# IPBUS_mezzanine.net
KiCad netlist of a schematic drawn in Altium Designer
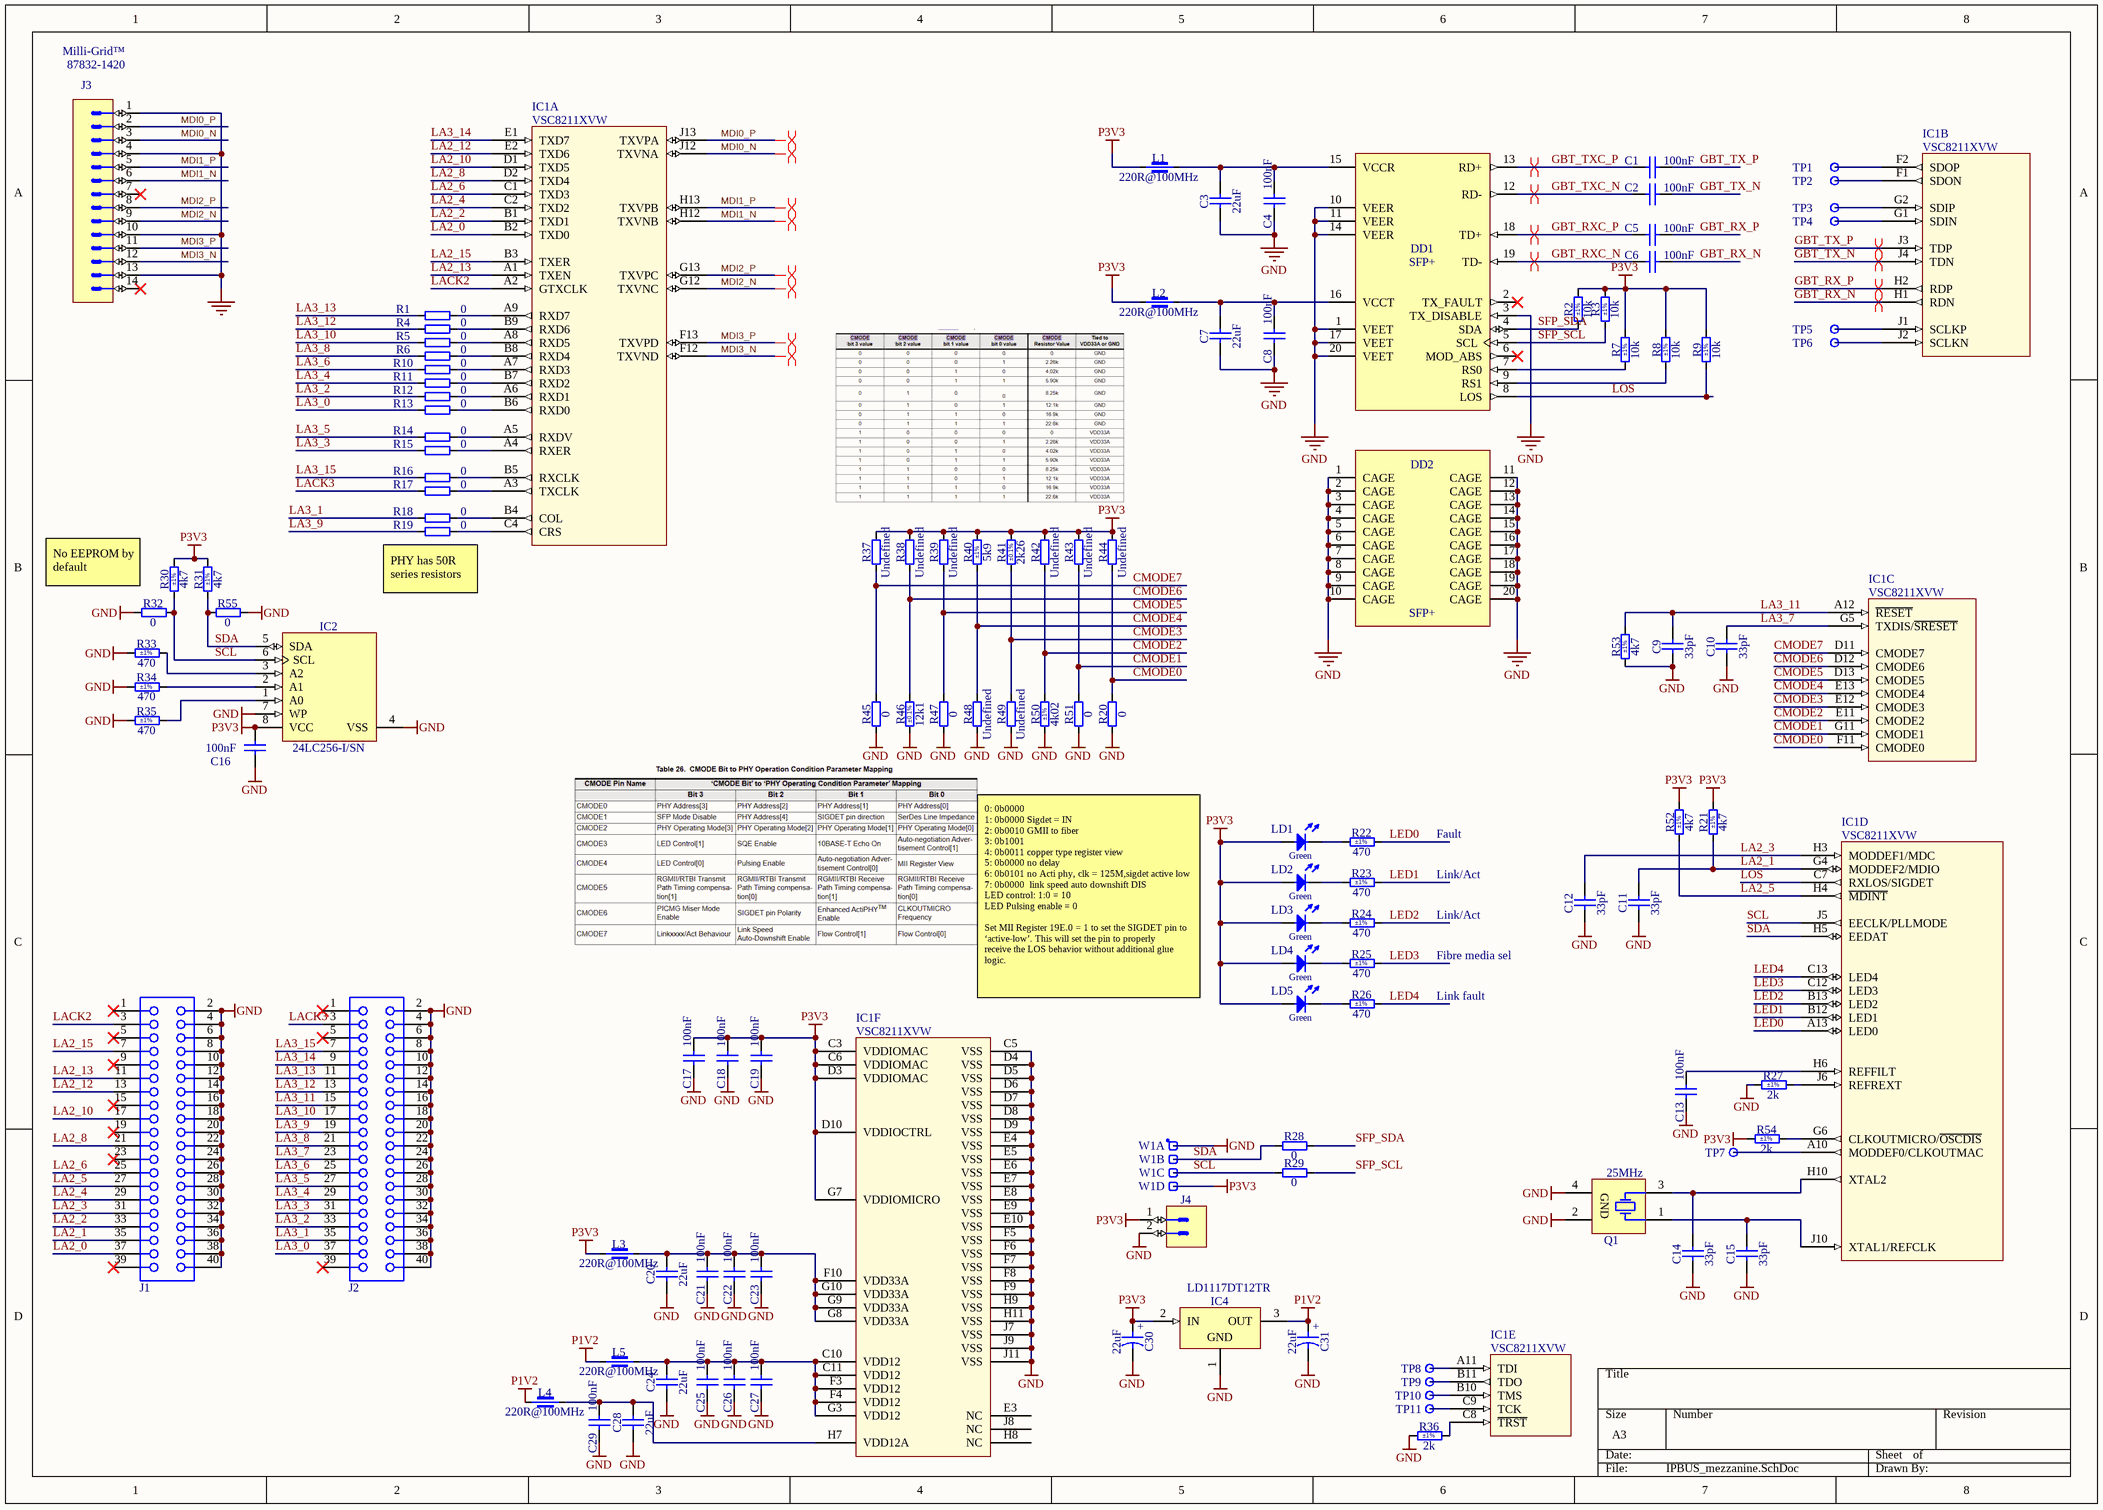
[diagram p0: IPBUS_mezzanine.SchDoc]

(export (version "E")
  (design (tool "Eeschema 10.0.6"))
  (components
    (comp (ref "C1")
      (value "100nF")
      (footprint "CAPC1005X55N")
      (description "Non-polarised capacitor")
      (fields
        (field (name "PART NUMBER") "CC0402_100NF_16V_10%_X5R")
        (field (name "VOLTAGE") "16V")
        (field (name "AUTHOR") "CERN DEM JLC")
      )
      (libsource (lib "Capacitors") (part "Capacitor - non polarized"))
    )
    (comp (ref "C2")
      (value "100nF")
      (footprint "CAPC1005X55N")
      (description "Non-polarised capacitor")
      (fields
        (field (name "PART NUMBER") "CC0402_100NF_16V_10%_X5R")
        (field (name "VOLTAGE") "16V")
        (field (name "AUTHOR") "CERN DEM JLC")
      )
      (libsource (lib "Capacitors") (part "Capacitor - non polarized"))
    )
    (comp (ref "C3")
      (value "22uF")
      (footprint "CAPC3216X180N")
      (description "Non-polarised capacitor")
      (fields
        (field (name "PART NUMBER") "CC1206_22UF_25V_20%_X5R")
        (field (name "VOLTAGE") "25V")
        (field (name "AUTHOR") "CERN DEM WB")
      )
      (libsource (lib "Capacitors") (part "Capacitor - non polarized"))
    )
    (comp (ref "C4")
      (value "100nF")
      (footprint "CAPC1005X55N")
      (description "Non-polarised capacitor")
      (fields
        (field (name "PART NUMBER") "CC0402_100NF_16V_10%_X5R")
        (field (name "VOLTAGE") "16V")
        (field (name "AUTHOR") "CERN DEM JLC")
      )
      (libsource (lib "Capacitors") (part "Capacitor - non polarized"))
    )
    (comp (ref "C5")
      (value "100nF")
      (footprint "CAPC1005X55N")
      (description "Non-polarised capacitor")
      (fields
        (field (name "PART NUMBER") "CC0402_100NF_16V_10%_X5R")
        (field (name "VOLTAGE") "16V")
        (field (name "AUTHOR") "CERN DEM JLC")
      )
      (libsource (lib "Capacitors") (part "Capacitor - non polarized"))
    )
    (comp (ref "C6")
      (value "100nF")
      (footprint "CAPC1005X55N")
      (description "Non-polarised capacitor")
      (fields
        (field (name "PART NUMBER") "CC0402_100NF_16V_10%_X5R")
        (field (name "VOLTAGE") "16V")
        (field (name "AUTHOR") "CERN DEM JLC")
      )
      (libsource (lib "Capacitors") (part "Capacitor - non polarized"))
    )
    (comp (ref "C7")
      (value "22uF")
      (footprint "CAPC3216X180N")
      (description "Non-polarised capacitor")
      (fields
        (field (name "PART NUMBER") "CC1206_22UF_25V_20%_X5R")
        (field (name "VOLTAGE") "25V")
        (field (name "AUTHOR") "CERN DEM WB")
      )
      (libsource (lib "Capacitors") (part "Capacitor - non polarized"))
    )
    (comp (ref "C8")
      (value "100nF")
      (footprint "CAPC1005X55N")
      (description "Non-polarised capacitor")
      (fields
        (field (name "PART NUMBER") "CC0402_100NF_16V_10%_X5R")
        (field (name "VOLTAGE") "16V")
        (field (name "AUTHOR") "CERN DEM JLC")
      )
      (libsource (lib "Capacitors") (part "Capacitor - non polarized"))
    )
    (comp (ref "C9")
      (value "33pF")
      (footprint "CAPC1005X55N")
      (description "Non-polarised capacitor")
      (fields
        (field (name "PART NUMBER") "CC0402_33PF_50V_5%_C0G")
        (field (name "VOLTAGE") "50V")
        (field (name "AUTHOR") "CERN DEM JLC")
      )
      (libsource (lib "Capacitors") (part "Capacitor - non polarized"))
    )
    (comp (ref "C10")
      (value "33pF")
      (footprint "CAPC1005X55N")
      (description "Non-polarised capacitor")
      (fields
        (field (name "PART NUMBER") "CC0402_33PF_50V_5%_C0G")
        (field (name "VOLTAGE") "50V")
        (field (name "AUTHOR") "CERN DEM JLC")
      )
      (libsource (lib "Capacitors") (part "Capacitor - non polarized"))
    )
    (comp (ref "C11")
      (value "33pF")
      (footprint "CAPC1005X55N")
      (description "Non-polarised capacitor")
      (fields
        (field (name "PART NUMBER") "CC0402_33PF_50V_5%_C0G")
        (field (name "VOLTAGE") "50V")
        (field (name "AUTHOR") "CERN DEM JLC")
      )
      (libsource (lib "Capacitors") (part "Capacitor - non polarized"))
    )
    (comp (ref "C12")
      (value "33pF")
      (footprint "CAPC1005X55N")
      (description "Non-polarised capacitor")
      (fields
        (field (name "PART NUMBER") "CC0402_33PF_50V_5%_C0G")
        (field (name "VOLTAGE") "50V")
        (field (name "AUTHOR") "CERN DEM JLC")
      )
      (libsource (lib "Capacitors") (part "Capacitor - non polarized"))
    )
    (comp (ref "C13")
      (value "100nF")
      (footprint "CAPC1005X55N")
      (description "Non-polarised capacitor")
      (fields
        (field (name "PART NUMBER") "CC0402_100NF_16V_10%_X5R")
        (field (name "VOLTAGE") "16V")
        (field (name "AUTHOR") "CERN DEM JLC")
      )
      (libsource (lib "Capacitors") (part "Capacitor - non polarized"))
    )
    (comp (ref "C14")
      (value "33pF")
      (footprint "CAPC1005X55N")
      (description "Non-polarised capacitor")
      (fields
        (field (name "PART NUMBER") "CC0402_33PF_50V_5%_C0G")
        (field (name "VOLTAGE") "50V")
        (field (name "AUTHOR") "CERN DEM JLC")
      )
      (libsource (lib "Capacitors") (part "Capacitor - non polarized"))
    )
    (comp (ref "C15")
      (value "33pF")
      (footprint "CAPC1005X55N")
      (description "Non-polarised capacitor")
      (fields
        (field (name "PART NUMBER") "CC0402_33PF_50V_5%_C0G")
        (field (name "VOLTAGE") "50V")
        (field (name "AUTHOR") "CERN DEM JLC")
      )
      (libsource (lib "Capacitors") (part "Capacitor - non polarized"))
    )
    (comp (ref "C16")
      (value "100nF")
      (footprint "CAPC1005X55N")
      (description "Non-polarised capacitor")
      (fields
        (field (name "PART NUMBER") "CC0402_100NF_16V_10%_X5R")
        (field (name "VOLTAGE") "16V")
        (field (name "AUTHOR") "CERN DEM JLC")
      )
      (libsource (lib "Capacitors") (part "Capacitor - non polarized"))
    )
    (comp (ref "C17")
      (value "100nF")
      (footprint "CAPC1005X55N")
      (description "Non-polarised capacitor")
      (fields
        (field (name "PART NUMBER") "CC0402_100NF_16V_10%_X5R")
        (field (name "VOLTAGE") "16V")
        (field (name "AUTHOR") "CERN DEM JLC")
      )
      (libsource (lib "Capacitors") (part "Capacitor - non polarized"))
    )
    (comp (ref "C18")
      (value "100nF")
      (footprint "CAPC1005X55N")
      (description "Non-polarised capacitor")
      (fields
        (field (name "PART NUMBER") "CC0402_100NF_16V_10%_X5R")
        (field (name "VOLTAGE") "16V")
        (field (name "AUTHOR") "CERN DEM JLC")
      )
      (libsource (lib "Capacitors") (part "Capacitor - non polarized"))
    )
    (comp (ref "C19")
      (value "100nF")
      (footprint "CAPC1005X55N")
      (description "Non-polarised capacitor")
      (fields
        (field (name "PART NUMBER") "CC0402_100NF_16V_10%_X5R")
        (field (name "VOLTAGE") "16V")
        (field (name "AUTHOR") "CERN DEM JLC")
      )
      (libsource (lib "Capacitors") (part "Capacitor - non polarized"))
    )
    (comp (ref "C20")
      (value "22uF")
      (footprint "CAPC3216X180N")
      (description "Non-polarised capacitor")
      (fields
        (field (name "PART NUMBER") "CC1206_22UF_25V_20%_X5R")
        (field (name "VOLTAGE") "25V")
        (field (name "AUTHOR") "CERN DEM WB")
      )
      (libsource (lib "Capacitors") (part "Capacitor - non polarized"))
    )
    (comp (ref "C21")
      (value "100nF")
      (footprint "CAPC1005X55N")
      (description "Non-polarised capacitor")
      (fields
        (field (name "PART NUMBER") "CC0402_100NF_16V_10%_X5R")
        (field (name "VOLTAGE") "16V")
        (field (name "AUTHOR") "CERN DEM JLC")
      )
      (libsource (lib "Capacitors") (part "Capacitor - non polarized"))
    )
    (comp (ref "C22")
      (value "100nF")
      (footprint "CAPC1005X55N")
      (description "Non-polarised capacitor")
      (fields
        (field (name "PART NUMBER") "CC0402_100NF_16V_10%_X5R")
        (field (name "VOLTAGE") "16V")
        (field (name "AUTHOR") "CERN DEM JLC")
      )
      (libsource (lib "Capacitors") (part "Capacitor - non polarized"))
    )
    (comp (ref "C23")
      (value "100nF")
      (footprint "CAPC1005X55N")
      (description "Non-polarised capacitor")
      (fields
        (field (name "PART NUMBER") "CC0402_100NF_16V_10%_X5R")
        (field (name "VOLTAGE") "16V")
        (field (name "AUTHOR") "CERN DEM JLC")
      )
      (libsource (lib "Capacitors") (part "Capacitor - non polarized"))
    )
    (comp (ref "C24")
      (value "22uF")
      (footprint "CAPC3216X180N")
      (description "Non-polarised capacitor")
      (fields
        (field (name "PART NUMBER") "CC1206_22UF_25V_20%_X5R")
        (field (name "VOLTAGE") "25V")
        (field (name "AUTHOR") "CERN DEM WB")
      )
      (libsource (lib "Capacitors") (part "Capacitor - non polarized"))
    )
    (comp (ref "C25")
      (value "100nF")
      (footprint "CAPC1005X55N")
      (description "Non-polarised capacitor")
      (fields
        (field (name "PART NUMBER") "CC0402_100NF_16V_10%_X5R")
        (field (name "VOLTAGE") "16V")
        (field (name "AUTHOR") "CERN DEM JLC")
      )
      (libsource (lib "Capacitors") (part "Capacitor - non polarized"))
    )
    (comp (ref "C26")
      (value "100nF")
      (footprint "CAPC1005X55N")
      (description "Non-polarised capacitor")
      (fields
        (field (name "PART NUMBER") "CC0402_100NF_16V_10%_X5R")
        (field (name "VOLTAGE") "16V")
        (field (name "AUTHOR") "CERN DEM JLC")
      )
      (libsource (lib "Capacitors") (part "Capacitor - non polarized"))
    )
    (comp (ref "C27")
      (value "100nF")
      (footprint "CAPC1005X55N")
      (description "Non-polarised capacitor")
      (fields
        (field (name "PART NUMBER") "CC0402_100NF_16V_10%_X5R")
        (field (name "VOLTAGE") "16V")
        (field (name "AUTHOR") "CERN DEM JLC")
      )
      (libsource (lib "Capacitors") (part "Capacitor - non polarized"))
    )
    (comp (ref "C28")
      (value "22uF")
      (footprint "CAPC3216X180N")
      (description "Non-polarised capacitor")
      (fields
        (field (name "PART NUMBER") "CC1206_22UF_25V_20%_X5R")
        (field (name "VOLTAGE") "25V")
        (field (name "AUTHOR") "CERN DEM WB")
      )
      (libsource (lib "Capacitors") (part "Capacitor - non polarized"))
    )
    (comp (ref "C29")
      (value "100nF")
      (footprint "CAPC1005X55N")
      (description "Non-polarised capacitor")
      (fields
        (field (name "PART NUMBER") "CC0402_100NF_16V_10%_X5R")
        (field (name "VOLTAGE") "16V")
        (field (name "AUTHOR") "CERN DEM JLC")
      )
      (libsource (lib "Capacitors") (part "Capacitor - non polarized"))
    )
    (comp (ref "C30")
      (value "22uF")
      (footprint "CAPMP3528X210N")
      (description "Polarised capacitor")
      (fields
        (field (name "PART NUMBER") "CTE3528-21_22UF_10V_10%_LESR0700")
        (field (name "VOLTAGE") "10V")
        (field (name "AUTHOR") "CERN DEM JLC")
      )
      (libsource (lib "Capacitors") (part "Capacitor - polarized"))
    )
    (comp (ref "C31")
      (value "22uF")
      (footprint "CAPMP3528X210N")
      (description "Polarised capacitor")
      (fields
        (field (name "PART NUMBER") "CTE3528-21_22UF_10V_10%_LESR0700")
        (field (name "VOLTAGE") "10V")
        (field (name "AUTHOR") "CERN DEM JLC")
      )
      (libsource (lib "Capacitors") (part "Capacitor - polarized"))
    )
    (comp (ref "DD1")
      (value "SFP+")
      (footprint "AMPHENOL_UE76A203000")
      (description "20 Position SFP+ Connector (Small Form-factor Pluggable)")
      (fields
        (field (name "PART NUMBER") "AMPHENOL_UE76A203000")
        (field (name "MANUFACTURER") "AMPHENOL")
        (field (name "AUTHOR") "CERN DEM BC")
      )
      (libsource (lib "Connectors") (part "SFP+x1"))
    )
    (comp (ref "DD2")
      (value "SFP+")
      (footprint "AMPHENOL_U77A16131001")
      (description "SFP+ 1x1 Cage (20Pins)")
      (fields
        (field (name "PART NUMBER") "AMPHENOL_U77A16131001")
        (field (name "MANUFACTURER") "AMPHENOL")
        (field (name "AUTHOR") "CERN DEM BC")
      )
      (libsource (lib "Connectors") (part "SFP+ 1x1 Cage (20Pins)"))
    )
    (comp (ref "IC1")
      (value "VSC8211XVW")
      (footprint "BGA117C100P13X9_1400X1000X170")
      (fields (field (name "MANUFACTURER") "VITESSE SEMICONDUCTOR") (field (name "AUTHOR") "CERN DEM JLC"))
      (libsource (lib "ICs And Semiconductors") (part "VSC8211XVW"))
    )
    (comp (ref "IC2")
      (value "24LC256-I/SN")
      (footprint "SOIC127P600X175-8N")
      (description "2.5V-5.5V, 256K (32k x 8-bit) I2C Serial EEPROM")
      (fields (field (name "MANUFACTURER") "MICROCHIP TECHNOLOGY") (field (name "AUTHOR") "CERN DEM JLC"))
      (libsource (lib "ICs And Semiconductors") (part "24LC256-I/SN"))
    )
    (comp (ref "IC4")
      (value "LD1117DT12TR")
      (footprint "TO228P972X240-3N-R540X510")
      (description "3-Terminal Regulator 1=GND 2=IN 3=OUT")
      (fields (field (name "MANUFACTURER") "ST MICROELECTRONICS") (field (name "AUTHOR") "CERN DEM JLC"))
      (libsource (lib "ICs And Semiconductors") (part "REG3 1GND-2IN-3OUT"))
    )
    (comp (ref "J1")
      (value "61304021821")
      (footprint "61304021821")
      (description "WR-PHD Socket Header, THT, Vertical, pitch 2.54mm, 2 Row, 40P")
      (fields (field (name "MANUFACTURER") "Wurth Elektronik"))
      (libsource (lib "Altium_WR-PHD (rev24a)") (part "61304021821"))
    )
    (comp (ref "J2")
      (value "61304021821")
      (footprint "61304021821")
      (description "WR-PHD Socket Header, THT, Vertical, pitch 2.54mm, 2 Row, 40P")
      (fields (field (name "MANUFACTURER") "Wurth Elektronik"))
      (libsource (lib "Altium_WR-PHD (rev24a)") (part "61304021821"))
    )
    (comp (ref "J3")
      (value "Milli-Grid™")
      (footprint "MOLEX_87832-1420")
      (description "Connector 14 Male")
      (fields
        (field (name "MANUFACTURER PART NUMBER") "87832-1420")
        (field (name "MANUFACTURER") "MOLEX")
        (field (name "PART NUMBER") "MOLEX_87832-1420")
        (field (name "AUTHOR") "CERN DEM JLC")
      )
      (libsource (lib "Connectors") (part "Connector 14 Male"))
    )
    (comp (ref "J4")
      (value "KK®")
      (footprint "MOLEX_22-05-7028")
      (description "Connector 2 Male")
      (fields
        (field (name "PART NUMBER") "MOLEX_22-05-7028")
        (field (name "MANUFACTURER") "MOLEX")
        (field (name "AUTHOR") "CERN DEM JLC")
      )
      (libsource (lib "Connectors") (part "Connector 2 Male"))
    )
    (comp (ref "L1")
      (value "220R@100MHz")
      (footprint "INDC1608X95N")
      (fields
        (field (name "PART NUMBER") "IND0603_MURATA_BLM18SG221TN1")
        (field (name "POWER") "2.5A")
        (field (name "TOLERANCE") "±25%")
        (field (name "AUTHOR") "CERN DEM MR")
      )
      (libsource (lib "Inductors & Transformers") (part "Ferrite Bead"))
    )
    (comp (ref "L2")
      (value "220R@100MHz")
      (footprint "INDC1608X95N")
      (fields
        (field (name "PART NUMBER") "IND0603_MURATA_BLM18SG221TN1")
        (field (name "POWER") "2.5A")
        (field (name "TOLERANCE") "±25%")
        (field (name "AUTHOR") "CERN DEM MR")
      )
      (libsource (lib "Inductors & Transformers") (part "Ferrite Bead"))
    )
    (comp (ref "L3")
      (value "220R@100MHz")
      (footprint "INDC1608X95N")
      (fields
        (field (name "PART NUMBER") "IND0603_MURATA_BLM18SG221TN1")
        (field (name "POWER") "2.5A")
        (field (name "TOLERANCE") "±25%")
        (field (name "AUTHOR") "CERN DEM MR")
      )
      (libsource (lib "Inductors & Transformers") (part "Ferrite Bead"))
    )
    (comp (ref "L4")
      (value "220R@100MHz")
      (footprint "INDC1608X95N")
      (fields
        (field (name "PART NUMBER") "IND0603_MURATA_BLM18SG221TN1")
        (field (name "POWER") "2.5A")
        (field (name "TOLERANCE") "±25%")
        (field (name "AUTHOR") "CERN DEM MR")
      )
      (libsource (lib "Inductors & Transformers") (part "Ferrite Bead"))
    )
    (comp (ref "L5")
      (value "220R@100MHz")
      (footprint "INDC1608X95N")
      (fields
        (field (name "PART NUMBER") "IND0603_MURATA_BLM18SG221TN1")
        (field (name "POWER") "2.5A")
        (field (name "TOLERANCE") "±25%")
        (field (name "AUTHOR") "CERN DEM MR")
      )
      (libsource (lib "Inductors & Transformers") (part "Ferrite Bead"))
    )
    (comp (ref "LD1")
      (value "Green")
      (footprint "LED_AVAGO_HSME-C120")
      (description "LED Green 1C 2A")
      (fields
        (field (name "PART NUMBER") "LED_AVAGO_HSME-C120")
        (field (name "MANUFACTURER") "AVAGO TECHNOLOGIES")
        (field (name "AUTHOR") "CERN DEM JMW")
      )
      (libsource (lib "ICs And Semiconductors") (part "LED Green 1C 2A"))
    )
    (comp (ref "LD2")
      (value "Green")
      (footprint "LED_AVAGO_HSME-C120")
      (description "LED Green 1C 2A")
      (fields
        (field (name "PART NUMBER") "LED_AVAGO_HSME-C120")
        (field (name "MANUFACTURER") "AVAGO TECHNOLOGIES")
        (field (name "AUTHOR") "CERN DEM JMW")
      )
      (libsource (lib "ICs And Semiconductors") (part "LED Green 1C 2A"))
    )
    (comp (ref "LD3")
      (value "Green")
      (footprint "LED_AVAGO_HSME-C120")
      (description "LED Green 1C 2A")
      (fields
        (field (name "PART NUMBER") "LED_AVAGO_HSME-C120")
        (field (name "MANUFACTURER") "AVAGO TECHNOLOGIES")
        (field (name "AUTHOR") "CERN DEM JMW")
      )
      (libsource (lib "ICs And Semiconductors") (part "LED Green 1C 2A"))
    )
    (comp (ref "LD4")
      (value "Green")
      (footprint "LED_AVAGO_HSME-C120")
      (description "LED Green 1C 2A")
      (fields
        (field (name "PART NUMBER") "LED_AVAGO_HSME-C120")
        (field (name "MANUFACTURER") "AVAGO TECHNOLOGIES")
        (field (name "AUTHOR") "CERN DEM JMW")
      )
      (libsource (lib "ICs And Semiconductors") (part "LED Green 1C 2A"))
    )
    (comp (ref "LD5")
      (value "Green")
      (footprint "LED_AVAGO_HSME-C120")
      (description "LED Green 1C 2A")
      (fields
        (field (name "PART NUMBER") "LED_AVAGO_HSME-C120")
        (field (name "MANUFACTURER") "AVAGO TECHNOLOGIES")
        (field (name "AUTHOR") "CERN DEM JMW")
      )
      (libsource (lib "ICs And Semiconductors") (part "LED Green 1C 2A"))
    )
    (comp (ref "Q1")
      (value "25MHz")
      (footprint "XTAL_TXC_8Y")
      (description "Crystal 4 pins 1=XTAL Control 2=GND3=XTAL 4=GND")
      (fields
        (field (name "PART NUMBER") "XTAL_25MHZ_TXC_8Y-25.000MAAJ-T")
        (field (name "MANUFACTURER") "TXC CORPORATION")
        (field (name "AUTHOR") "CERN DEM JLC")
      )
      (libsource (lib "ICs And Semiconductors") (part "Quartz Crystal 1X 2GND 3X 4GND"))
    )
    (comp (ref "R1")
      (value "0")
      (footprint "RESC1005X40N")
      (description "Resistor")
      (fields
        (field (name "PART NUMBER") "R0402_0R_JUMPER")
        (field (name "MANUFACTURER") "GENERIC")
        (field (name "AUTHOR") "CERN DEM JLC")
      )
      (libsource (lib "Resistors") (part "Resistor"))
    )
    (comp (ref "R2")
      (value "10k")
      (footprint "RESC1608X55N")
      (description "Resistor - 1%")
      (fields
        (field (name "TOLERANCE") "±1%")
        (field (name "PART NUMBER") "R0603_10K_1%_0.1W_100PPM")
        (field (name "POWER") "0.1W")
        (field (name "AUTHOR") "CERN DEM JLC")
      )
      (libsource (lib "Resistors") (part "Resistor - 1%"))
    )
    (comp (ref "R3")
      (value "10k")
      (footprint "RESC1608X55N")
      (description "Resistor - 1%")
      (fields
        (field (name "TOLERANCE") "±1%")
        (field (name "PART NUMBER") "R0603_10K_1%_0.1W_100PPM")
        (field (name "POWER") "0.1W")
        (field (name "AUTHOR") "CERN DEM JLC")
      )
      (libsource (lib "Resistors") (part "Resistor - 1%"))
    )
    (comp (ref "R4")
      (value "0")
      (footprint "RESC1005X40N")
      (description "Resistor")
      (fields
        (field (name "PART NUMBER") "R0402_0R_JUMPER")
        (field (name "MANUFACTURER") "GENERIC")
        (field (name "AUTHOR") "CERN DEM JLC")
      )
      (libsource (lib "Resistors") (part "Resistor"))
    )
    (comp (ref "R5")
      (value "0")
      (footprint "RESC1005X40N")
      (description "Resistor")
      (fields
        (field (name "PART NUMBER") "R0402_0R_JUMPER")
        (field (name "MANUFACTURER") "GENERIC")
        (field (name "AUTHOR") "CERN DEM JLC")
      )
      (libsource (lib "Resistors") (part "Resistor"))
    )
    (comp (ref "R6")
      (value "0")
      (footprint "RESC1005X40N")
      (description "Resistor")
      (fields
        (field (name "PART NUMBER") "R0402_0R_JUMPER")
        (field (name "MANUFACTURER") "GENERIC")
        (field (name "AUTHOR") "CERN DEM JLC")
      )
      (libsource (lib "Resistors") (part "Resistor"))
    )
    (comp (ref "R7")
      (value "10k")
      (footprint "RESC1608X55N")
      (description "Resistor - 1%")
      (fields
        (field (name "TOLERANCE") "±1%")
        (field (name "PART NUMBER") "R0603_10K_1%_0.1W_100PPM")
        (field (name "POWER") "0.1W")
        (field (name "AUTHOR") "CERN DEM JLC")
      )
      (libsource (lib "Resistors") (part "Resistor - 1%"))
    )
    (comp (ref "R8")
      (value "10k")
      (footprint "RESC1608X55N")
      (description "Resistor - 1%")
      (fields
        (field (name "TOLERANCE") "±1%")
        (field (name "PART NUMBER") "R0603_10K_1%_0.1W_100PPM")
        (field (name "POWER") "0.1W")
        (field (name "AUTHOR") "CERN DEM JLC")
      )
      (libsource (lib "Resistors") (part "Resistor - 1%"))
    )
    (comp (ref "R9")
      (value "10k")
      (footprint "RESC1608X55N")
      (description "Resistor - 1%")
      (fields
        (field (name "TOLERANCE") "±1%")
        (field (name "PART NUMBER") "R0603_10K_1%_0.1W_100PPM")
        (field (name "POWER") "0.1W")
        (field (name "AUTHOR") "CERN DEM JLC")
      )
      (libsource (lib "Resistors") (part "Resistor - 1%"))
    )
    (comp (ref "R10")
      (value "0")
      (footprint "RESC1005X40N")
      (description "Resistor")
      (fields
        (field (name "PART NUMBER") "R0402_0R_JUMPER")
        (field (name "MANUFACTURER") "GENERIC")
        (field (name "AUTHOR") "CERN DEM JLC")
      )
      (libsource (lib "Resistors") (part "Resistor"))
    )
    (comp (ref "R11")
      (value "0")
      (footprint "RESC1005X40N")
      (description "Resistor")
      (fields
        (field (name "PART NUMBER") "R0402_0R_JUMPER")
        (field (name "MANUFACTURER") "GENERIC")
        (field (name "AUTHOR") "CERN DEM JLC")
      )
      (libsource (lib "Resistors") (part "Resistor"))
    )
    (comp (ref "R12")
      (value "0")
      (footprint "RESC1005X40N")
      (description "Resistor")
      (fields
        (field (name "PART NUMBER") "R0402_0R_JUMPER")
        (field (name "MANUFACTURER") "GENERIC")
        (field (name "AUTHOR") "CERN DEM JLC")
      )
      (libsource (lib "Resistors") (part "Resistor"))
    )
    (comp (ref "R13")
      (value "0")
      (footprint "RESC1005X40N")
      (description "Resistor")
      (fields
        (field (name "PART NUMBER") "R0402_0R_JUMPER")
        (field (name "MANUFACTURER") "GENERIC")
        (field (name "AUTHOR") "CERN DEM JLC")
      )
      (libsource (lib "Resistors") (part "Resistor"))
    )
    (comp (ref "R14")
      (value "0")
      (footprint "RESC1005X40N")
      (description "Resistor")
      (fields
        (field (name "PART NUMBER") "R0402_0R_JUMPER")
        (field (name "MANUFACTURER") "GENERIC")
        (field (name "AUTHOR") "CERN DEM JLC")
      )
      (libsource (lib "Resistors") (part "Resistor"))
    )
    (comp (ref "R15")
      (value "0")
      (footprint "RESC1005X40N")
      (description "Resistor")
      (fields
        (field (name "PART NUMBER") "R0402_0R_JUMPER")
        (field (name "MANUFACTURER") "GENERIC")
        (field (name "AUTHOR") "CERN DEM JLC")
      )
      (libsource (lib "Resistors") (part "Resistor"))
    )
    (comp (ref "R16")
      (value "0")
      (footprint "RESC1005X40N")
      (description "Resistor")
      (fields
        (field (name "PART NUMBER") "R0402_0R_JUMPER")
        (field (name "MANUFACTURER") "GENERIC")
        (field (name "AUTHOR") "CERN DEM JLC")
      )
      (libsource (lib "Resistors") (part "Resistor"))
    )
    (comp (ref "R17")
      (value "0")
      (footprint "RESC1005X40N")
      (description "Resistor")
      (fields
        (field (name "PART NUMBER") "R0402_0R_JUMPER")
        (field (name "MANUFACTURER") "GENERIC")
        (field (name "AUTHOR") "CERN DEM JLC")
      )
      (libsource (lib "Resistors") (part "Resistor"))
    )
    (comp (ref "R18")
      (value "0")
      (footprint "RESC1005X40N")
      (description "Resistor")
      (fields
        (field (name "PART NUMBER") "R0402_0R_JUMPER")
        (field (name "MANUFACTURER") "GENERIC")
        (field (name "AUTHOR") "CERN DEM JLC")
      )
      (libsource (lib "Resistors") (part "Resistor"))
    )
    (comp (ref "R19")
      (value "0")
      (footprint "RESC1005X40N")
      (description "Resistor")
      (fields
        (field (name "PART NUMBER") "R0402_0R_JUMPER")
        (field (name "MANUFACTURER") "GENERIC")
        (field (name "AUTHOR") "CERN DEM JLC")
      )
      (libsource (lib "Resistors") (part "Resistor"))
    )
    (comp (ref "R20")
      (value "0")
      (footprint "RESC1608X55N")
      (description "Resistor")
      (fields
        (field (name "PART NUMBER") "R0603_0R_JUMPER")
        (field (name "MANUFACTURER") "GENERIC")
        (field (name "AUTHOR") "CERN DEM JLC")
      )
      (libsource (lib "Resistors") (part "Resistor"))
    )
    (comp (ref "R21")
      (value "4k7")
      (footprint "RESC1608X55N")
      (description "Resistor - 1%")
      (fields
        (field (name "TOLERANCE") "±1%")
        (field (name "PART NUMBER") "R0603_4K7_1%_0.1W_100PPM")
        (field (name "POWER") "0.1W")
        (field (name "AUTHOR") "CERN DEM JLC")
      )
      (libsource (lib "Resistors") (part "Resistor - 1%"))
    )
    (comp (ref "R22")
      (value "470")
      (footprint "RESC1608X55N")
      (description "Resistor - 1%")
      (fields
        (field (name "TOLERANCE") "±1%")
        (field (name "PART NUMBER") "R0603_470R_1%_0.1W_100PPM")
        (field (name "POWER") "0.1W")
        (field (name "AUTHOR") "CERN DEM JLC")
      )
      (libsource (lib "Resistors") (part "Resistor - 1%"))
    )
    (comp (ref "R23")
      (value "470")
      (footprint "RESC1608X55N")
      (description "Resistor - 1%")
      (fields
        (field (name "TOLERANCE") "±1%")
        (field (name "PART NUMBER") "R0603_470R_1%_0.1W_100PPM")
        (field (name "POWER") "0.1W")
        (field (name "AUTHOR") "CERN DEM JLC")
      )
      (libsource (lib "Resistors") (part "Resistor - 1%"))
    )
    (comp (ref "R24")
      (value "470")
      (footprint "RESC1608X55N")
      (description "Resistor - 1%")
      (fields
        (field (name "TOLERANCE") "±1%")
        (field (name "PART NUMBER") "R0603_470R_1%_0.1W_100PPM")
        (field (name "POWER") "0.1W")
        (field (name "AUTHOR") "CERN DEM JLC")
      )
      (libsource (lib "Resistors") (part "Resistor - 1%"))
    )
    (comp (ref "R25")
      (value "470")
      (footprint "RESC1608X55N")
      (description "Resistor - 1%")
      (fields
        (field (name "TOLERANCE") "±1%")
        (field (name "PART NUMBER") "R0603_470R_1%_0.1W_100PPM")
        (field (name "POWER") "0.1W")
        (field (name "AUTHOR") "CERN DEM JLC")
      )
      (libsource (lib "Resistors") (part "Resistor - 1%"))
    )
    (comp (ref "R26")
      (value "470")
      (footprint "RESC1608X55N")
      (description "Resistor - 1%")
      (fields
        (field (name "TOLERANCE") "±1%")
        (field (name "PART NUMBER") "R0603_470R_1%_0.1W_100PPM")
        (field (name "POWER") "0.1W")
        (field (name "AUTHOR") "CERN DEM JLC")
      )
      (libsource (lib "Resistors") (part "Resistor - 1%"))
    )
    (comp (ref "R27")
      (value "2k")
      (footprint "RESC1608X55N")
      (description "Resistor - 1%")
      (fields
        (field (name "TOLERANCE") "±1%")
        (field (name "PART NUMBER") "R0603_2K_1%_0.1W_100PPM")
        (field (name "POWER") "0.1W")
        (field (name "AUTHOR") "CERN DEM JLC")
      )
      (libsource (lib "Resistors") (part "Resistor - 1%"))
    )
    (comp (ref "R28")
      (value "0")
      (footprint "RESC1608X55N")
      (description "Resistor")
      (fields
        (field (name "PART NUMBER") "R0603_0R_JUMPER")
        (field (name "MANUFACTURER") "GENERIC")
        (field (name "AUTHOR") "CERN DEM JLC")
      )
      (libsource (lib "Resistors") (part "Resistor"))
    )
    (comp (ref "R29")
      (value "0")
      (footprint "RESC1608X55N")
      (description "Resistor")
      (fields
        (field (name "PART NUMBER") "R0603_0R_JUMPER")
        (field (name "MANUFACTURER") "GENERIC")
        (field (name "AUTHOR") "CERN DEM JLC")
      )
      (libsource (lib "Resistors") (part "Resistor"))
    )
    (comp (ref "R30")
      (value "4k7")
      (footprint "RESC1608X55N")
      (description "Resistor - 1%")
      (fields
        (field (name "TOLERANCE") "±1%")
        (field (name "PART NUMBER") "R0603_4K7_1%_0.1W_100PPM")
        (field (name "POWER") "0.1W")
        (field (name "AUTHOR") "CERN DEM JLC")
      )
      (libsource (lib "Resistors") (part "Resistor - 1%"))
    )
    (comp (ref "R31")
      (value "4k7")
      (footprint "RESC1608X55N")
      (description "Resistor - 1%")
      (fields
        (field (name "TOLERANCE") "±1%")
        (field (name "PART NUMBER") "R0603_4K7_1%_0.1W_100PPM")
        (field (name "POWER") "0.1W")
        (field (name "AUTHOR") "CERN DEM JLC")
      )
      (libsource (lib "Resistors") (part "Resistor - 1%"))
    )
    (comp (ref "R32")
      (value "0")
      (footprint "RESC1608X55N")
      (description "Resistor")
      (fields
        (field (name "PART NUMBER") "R0603_0R_JUMPER")
        (field (name "MANUFACTURER") "GENERIC")
        (field (name "AUTHOR") "CERN DEM JLC")
      )
      (libsource (lib "Resistors") (part "Resistor"))
    )
    (comp (ref "R33")
      (value "470")
      (footprint "RESC1608X55N")
      (description "Resistor - 1%")
      (fields
        (field (name "TOLERANCE") "±1%")
        (field (name "PART NUMBER") "R0603_470R_1%_0.1W_100PPM")
        (field (name "POWER") "0.1W")
        (field (name "AUTHOR") "CERN DEM JLC")
      )
      (libsource (lib "Resistors") (part "Resistor - 1%"))
    )
    (comp (ref "R34")
      (value "470")
      (footprint "RESC1608X55N")
      (description "Resistor - 1%")
      (fields
        (field (name "TOLERANCE") "±1%")
        (field (name "PART NUMBER") "R0603_470R_1%_0.1W_100PPM")
        (field (name "POWER") "0.1W")
        (field (name "AUTHOR") "CERN DEM JLC")
      )
      (libsource (lib "Resistors") (part "Resistor - 1%"))
    )
    (comp (ref "R35")
      (value "470")
      (footprint "RESC1608X55N")
      (description "Resistor - 1%")
      (fields
        (field (name "TOLERANCE") "±1%")
        (field (name "PART NUMBER") "R0603_470R_1%_0.1W_100PPM")
        (field (name "POWER") "0.1W")
        (field (name "AUTHOR") "CERN DEM JLC")
      )
      (libsource (lib "Resistors") (part "Resistor - 1%"))
    )
    (comp (ref "R36")
      (value "2k")
      (footprint "RESC1608X55N")
      (description "Resistor - 1%")
      (fields
        (field (name "TOLERANCE") "±1%")
        (field (name "PART NUMBER") "R0603_2K_1%_0.1W_100PPM")
        (field (name "POWER") "0.1W")
        (field (name "AUTHOR") "CERN DEM JLC")
      )
      (libsource (lib "Resistors") (part "Resistor - 1%"))
    )
    (comp (ref "R37")
      (value "Undefined")
      (footprint "RESC1608X55N")
      (description "Resistor")
      (fields (field (name "PART NUMBER") "R0603_NO-VALUE") (field (name "AUTHOR") "CERN DEM JLC"))
      (libsource (lib "Resistors") (part "Resistor"))
    )
    (comp (ref "R38")
      (value "Undefined")
      (footprint "RESC1608X55N")
      (description "Resistor")
      (fields (field (name "PART NUMBER") "R0603_NO-VALUE") (field (name "AUTHOR") "CERN DEM JLC"))
      (libsource (lib "Resistors") (part "Resistor"))
    )
    (comp (ref "R39")
      (value "Undefined")
      (footprint "RESC1608X55N")
      (description "Resistor")
      (fields (field (name "PART NUMBER") "R0603_NO-VALUE") (field (name "AUTHOR") "CERN DEM JLC"))
      (libsource (lib "Resistors") (part "Resistor"))
    )
    (comp (ref "R40")
      (value "5k9")
      (footprint "RESC1608X55N")
      (description "Resistor - 1%")
      (fields
        (field (name "PART NUMBER") "R0603_5K9_1%_0.1W_100PPM")
        (field (name "MANUFACTURER") "GENERIC")
        (field (name "TOLERANCE") "±1%")
        (field (name "AUTHOR") "CERN DEM JLC")
      )
      (libsource (lib "Resistors") (part "Resistor - 1%"))
    )
    (comp (ref "R41")
      (value "2k26")
      (footprint "RESC1608X55N")
      (description "Resistor - 0.1%")
      (fields
        (field (name "PART NUMBER") "R0603_2K26_0.1%_0.063W_10PPM")
        (field (name "MANUFACTURER") "GENERIC")
        (field (name "TOLERANCE") "±0.1%")
        (field (name "AUTHOR") "CERN DEM JLC")
      )
      (libsource (lib "Resistors") (part "Resistor - 0.1%"))
    )
    (comp (ref "R42")
      (value "Undefined")
      (footprint "RESC1608X55N")
      (description "Resistor")
      (fields (field (name "PART NUMBER") "R0603_NO-VALUE") (field (name "AUTHOR") "CERN DEM JLC"))
      (libsource (lib "Resistors") (part "Resistor"))
    )
    (comp (ref "R43")
      (value "Undefined")
      (footprint "RESC1608X55N")
      (description "Resistor")
      (fields (field (name "PART NUMBER") "R0603_NO-VALUE") (field (name "AUTHOR") "CERN DEM JLC"))
      (libsource (lib "Resistors") (part "Resistor"))
    )
    (comp (ref "R44")
      (value "Undefined")
      (footprint "RESC1608X55N")
      (description "Resistor")
      (fields (field (name "PART NUMBER") "R0603_NO-VALUE") (field (name "AUTHOR") "CERN DEM JLC"))
      (libsource (lib "Resistors") (part "Resistor"))
    )
    (comp (ref "R45")
      (value "0")
      (footprint "RESC1608X55N")
      (description "Resistor")
      (fields
        (field (name "PART NUMBER") "R0603_0R_JUMPER")
        (field (name "MANUFACTURER") "GENERIC")
        (field (name "AUTHOR") "CERN DEM JLC")
      )
      (libsource (lib "Resistors") (part "Resistor"))
    )
    (comp (ref "R46")
      (value "12k1")
      (footprint "RESC1608X55N")
      (description "Resistor - 0.1%")
      (fields
        (field (name "PART NUMBER") "R0603_12K1_0.1%_0.063W_10PPM")
        (field (name "MANUFACTURER") "GENERIC")
        (field (name "TOLERANCE") "±0.1%")
        (field (name "AUTHOR") "CERN DEM JLC")
      )
      (libsource (lib "Resistors") (part "Resistor - 0.1%"))
    )
    (comp (ref "R47")
      (value "0")
      (footprint "RESC1608X55N")
      (description "Resistor")
      (fields
        (field (name "PART NUMBER") "R0603_0R_JUMPER")
        (field (name "MANUFACTURER") "GENERIC")
        (field (name "AUTHOR") "CERN DEM JLC")
      )
      (libsource (lib "Resistors") (part "Resistor"))
    )
    (comp (ref "R48")
      (value "Undefined")
      (footprint "RESC1608X55N")
      (description "Resistor")
      (fields (field (name "PART NUMBER") "R0603_NO-VALUE") (field (name "AUTHOR") "CERN DEM JLC"))
      (libsource (lib "Resistors") (part "Resistor"))
    )
    (comp (ref "R49")
      (value "Undefined")
      (footprint "RESC1608X55N")
      (description "Resistor")
      (fields (field (name "PART NUMBER") "R0603_NO-VALUE") (field (name "AUTHOR") "CERN DEM JLC"))
      (libsource (lib "Resistors") (part "Resistor"))
    )
    (comp (ref "R50")
      (value "4k02")
      (footprint "RESC1608X55N")
      (description "Resistor - 1%")
      (fields
        (field (name "PART NUMBER") "R0603_4K02_1%_0.1W_100PPM")
        (field (name "MANUFACTURER") "GENERIC")
        (field (name "TOLERANCE") "±1%")
        (field (name "AUTHOR") "CERN DEM BC")
      )
      (libsource (lib "Resistors") (part "Resistor - 1%"))
    )
    (comp (ref "R51")
      (value "0")
      (footprint "RESC1608X55N")
      (description "Resistor")
      (fields
        (field (name "PART NUMBER") "R0603_0R_JUMPER")
        (field (name "MANUFACTURER") "GENERIC")
        (field (name "AUTHOR") "CERN DEM JLC")
      )
      (libsource (lib "Resistors") (part "Resistor"))
    )
    (comp (ref "R52")
      (value "4k7")
      (footprint "RESC1608X55N")
      (description "Resistor - 1%")
      (fields
        (field (name "TOLERANCE") "±1%")
        (field (name "PART NUMBER") "R0603_4K7_1%_0.1W_100PPM")
        (field (name "POWER") "0.1W")
        (field (name "AUTHOR") "CERN DEM JLC")
      )
      (libsource (lib "Resistors") (part "Resistor - 1%"))
    )
    (comp (ref "R53")
      (value "4k7")
      (footprint "RESC1608X55N")
      (description "Resistor - 1%")
      (fields
        (field (name "TOLERANCE") "±1%")
        (field (name "PART NUMBER") "R0603_4K7_1%_0.1W_100PPM")
        (field (name "POWER") "0.1W")
        (field (name "AUTHOR") "CERN DEM JLC")
      )
      (libsource (lib "Resistors") (part "Resistor - 1%"))
    )
    (comp (ref "R54")
      (value "2k")
      (footprint "RESC1608X55N")
      (description "Resistor - 1%")
      (fields
        (field (name "TOLERANCE") "±1%")
        (field (name "PART NUMBER") "R0603_2K_1%_0.1W_100PPM")
        (field (name "POWER") "0.1W")
        (field (name "AUTHOR") "CERN DEM JLC")
      )
      (libsource (lib "Resistors") (part "Resistor - 1%"))
    )
    (comp (ref "R55")
      (value "0")
      (footprint "RESC1608X55N")
      (description "Resistor")
      (fields
        (field (name "PART NUMBER") "R0603_0R_JUMPER")
        (field (name "MANUFACTURER") "GENERIC")
        (field (name "AUTHOR") "CERN DEM JLC")
      )
      (libsource (lib "Resistors") (part "Resistor"))
    )
    (comp (ref "TP1")
      (value "SMD Pad")
      (footprint "C60")
      (description "Test Point")
      (fields (field (name "PART NUMBER") "SMD_PAD_D0.6MM") (field (name "AUTHOR") "CERN DEM HF"))
      (libsource (lib "Eletro-mechanical") (part "Test Point"))
    )
    (comp (ref "TP2")
      (value "SMD Pad")
      (footprint "C60")
      (description "Test Point")
      (fields (field (name "PART NUMBER") "SMD_PAD_D0.6MM") (field (name "AUTHOR") "CERN DEM HF"))
      (libsource (lib "Eletro-mechanical") (part "Test Point"))
    )
    (comp (ref "TP3")
      (value "SMD Pad")
      (footprint "C60")
      (description "Test Point")
      (fields (field (name "PART NUMBER") "SMD_PAD_D0.6MM") (field (name "AUTHOR") "CERN DEM HF"))
      (libsource (lib "Eletro-mechanical") (part "Test Point"))
    )
    (comp (ref "TP4")
      (value "SMD Pad")
      (footprint "C60")
      (description "Test Point")
      (fields (field (name "PART NUMBER") "SMD_PAD_D0.6MM") (field (name "AUTHOR") "CERN DEM HF"))
      (libsource (lib "Eletro-mechanical") (part "Test Point"))
    )
    (comp (ref "TP5")
      (value "SMD Pad")
      (footprint "C60")
      (description "Test Point")
      (fields (field (name "PART NUMBER") "SMD_PAD_D0.6MM") (field (name "AUTHOR") "CERN DEM HF"))
      (libsource (lib "Eletro-mechanical") (part "Test Point"))
    )
    (comp (ref "TP6")
      (value "SMD Pad")
      (footprint "C60")
      (description "Test Point")
      (fields (field (name "PART NUMBER") "SMD_PAD_D0.6MM") (field (name "AUTHOR") "CERN DEM HF"))
      (libsource (lib "Eletro-mechanical") (part "Test Point"))
    )
    (comp (ref "TP7")
      (value "SMD Pad")
      (footprint "C60")
      (description "Test Point")
      (fields (field (name "PART NUMBER") "SMD_PAD_D0.6MM") (field (name "AUTHOR") "CERN DEM HF"))
      (libsource (lib "Eletro-mechanical") (part "Test Point"))
    )
    (comp (ref "TP8")
      (value "SMD Pad")
      (footprint "C60")
      (description "Test Point")
      (fields (field (name "PART NUMBER") "SMD_PAD_D0.6MM") (field (name "AUTHOR") "CERN DEM HF"))
      (libsource (lib "Eletro-mechanical") (part "Test Point"))
    )
    (comp (ref "TP9")
      (value "SMD Pad")
      (footprint "C60")
      (description "Test Point")
      (fields (field (name "PART NUMBER") "SMD_PAD_D0.6MM") (field (name "AUTHOR") "CERN DEM HF"))
      (libsource (lib "Eletro-mechanical") (part "Test Point"))
    )
    (comp (ref "TP10")
      (value "SMD Pad")
      (footprint "C60")
      (description "Test Point")
      (fields (field (name "PART NUMBER") "SMD_PAD_D0.6MM") (field (name "AUTHOR") "CERN DEM HF"))
      (libsource (lib "Eletro-mechanical") (part "Test Point"))
    )
    (comp (ref "TP11")
      (value "SMD Pad")
      (footprint "C60")
      (description "Test Point")
      (fields (field (name "PART NUMBER") "SMD_PAD_D0.6MM") (field (name "AUTHOR") "CERN DEM HF"))
      (libsource (lib "Eletro-mechanical") (part "Test Point"))
    )
    (comp (ref "W1")
      (value "Header 4")
      (footprint "SAMTEC_HTSW-104-23-L-S")
      (description "4 Mini Wire-Wrap Contact Strip Header")
      (fields
        (field (name "PART NUMBER") "SAMTEC_HTSW-104-23-L-S")
        (field (name "MANUFACTURER") "SAMTEC")
        (field (name "AUTHOR") "CERN DEM JLC")
      )
      (libsource (lib "Connectors") (part "Wire-Wrap Contact x4"))
    )
  )
  (nets
    (net (code "1") (name "/CMODE0") (class "Default")
      (node (ref "IC1") (pin "F11") (pinfunction "CMODE0_F11") (pintype "input"))
      (node (ref "R20") (pin "2") (pinfunction "2_2") (pintype "passive"))
      (node (ref "R44") (pin "1") (pinfunction "1_1") (pintype "passive"))
    )
    (net (code "2") (name "/CMODE1") (class "Default")
      (node (ref "IC1") (pin "G11") (pinfunction "CMODE1_G11") (pintype "input"))
      (node (ref "R43") (pin "1") (pinfunction "1_1") (pintype "passive"))
      (node (ref "R51") (pin "2") (pinfunction "2_2") (pintype "passive"))
    )
    (net (code "3") (name "/CMODE2") (class "Default")
      (node (ref "IC1") (pin "E11") (pinfunction "CMODE2_E11") (pintype "input"))
      (node (ref "R42") (pin "1") (pinfunction "1_1") (pintype "passive"))
      (node (ref "R50") (pin "2") (pinfunction "2_2") (pintype "passive"))
    )
    (net (code "4") (name "/CMODE3") (class "Default")
      (node (ref "IC1") (pin "E12") (pinfunction "CMODE3_E12") (pintype "input"))
      (node (ref "R41") (pin "1") (pinfunction "1_1") (pintype "passive"))
      (node (ref "R49") (pin "2") (pinfunction "2_2") (pintype "passive"))
    )
    (net (code "5") (name "/CMODE4") (class "Default")
      (node (ref "IC1") (pin "E13") (pinfunction "CMODE4_E13") (pintype "input"))
      (node (ref "R40") (pin "1") (pinfunction "1_1") (pintype "passive"))
      (node (ref "R48") (pin "2") (pinfunction "2_2") (pintype "passive"))
    )
    (net (code "6") (name "/CMODE5") (class "Default")
      (node (ref "IC1") (pin "D13") (pinfunction "CMODE5_D13") (pintype "input"))
      (node (ref "R39") (pin "1") (pinfunction "1_1") (pintype "passive"))
      (node (ref "R47") (pin "2") (pinfunction "2_2") (pintype "passive"))
    )
    (net (code "7") (name "/CMODE6") (class "Default")
      (node (ref "IC1") (pin "D12") (pinfunction "CMODE6_D12") (pintype "input"))
      (node (ref "R38") (pin "1") (pinfunction "1_1") (pintype "passive"))
      (node (ref "R46") (pin "2") (pinfunction "2_2") (pintype "passive"))
    )
    (net (code "8") (name "/CMODE7") (class "Default")
      (node (ref "IC1") (pin "D11") (pinfunction "CMODE7_D11") (pintype "input"))
      (node (ref "R37") (pin "1") (pinfunction "1_1") (pintype "passive"))
      (node (ref "R45") (pin "2") (pinfunction "2_2") (pintype "passive"))
    )
    (net (code "9") (name "/GBT_RXC_N") (class "Default")
      (node (ref "C6") (pin "1") (pinfunction "1_1") (pintype "passive"))
      (node (ref "DD1") (pin "19") (pinfunction "TD-_19") (pintype "input"))
    )
    (net (code "10") (name "/GBT_RXC_P") (class "Default")
      (node (ref "C5") (pin "1") (pinfunction "1_1") (pintype "passive"))
      (node (ref "DD1") (pin "18") (pinfunction "TD+_18") (pintype "input"))
    )
    (net (code "11") (name "/GBT_RX_N") (class "Default")
      (node (ref "C6") (pin "2") (pinfunction "2_2") (pintype "passive"))
      (node (ref "IC1") (pin "H1") (pinfunction "RDN_H1") (pintype "output"))
    )
    (net (code "12") (name "/GBT_RX_P") (class "Default")
      (node (ref "C5") (pin "2") (pinfunction "2_2") (pintype "passive"))
      (node (ref "IC1") (pin "H2") (pinfunction "RDP_H2") (pintype "output"))
    )
    (net (code "13") (name "/GBT_TXC_N") (class "Default")
      (node (ref "C2") (pin "1") (pinfunction "1_1") (pintype "passive"))
      (node (ref "DD1") (pin "12") (pinfunction "RD-_12") (pintype "output"))
    )
    (net (code "14") (name "/GBT_TXC_P") (class "Default")
      (node (ref "C1") (pin "1") (pinfunction "1_1") (pintype "passive"))
      (node (ref "DD1") (pin "13") (pinfunction "RD+_13") (pintype "output"))
    )
    (net (code "15") (name "/GBT_TX_N") (class "Default")
      (node (ref "C2") (pin "2") (pinfunction "2_2") (pintype "passive"))
      (node (ref "IC1") (pin "J4") (pinfunction "TDN_J4") (pintype "input"))
    )
    (net (code "16") (name "/GBT_TX_P") (class "Default")
      (node (ref "C1") (pin "2") (pinfunction "2_2") (pintype "passive"))
      (node (ref "IC1") (pin "J3") (pinfunction "TDP_J3") (pintype "input"))
    )
    (net (code "17") (name "/LA2_0") (class "Default")
      (node (ref "IC1") (pin "B2") (pinfunction "TXD0_B2") (pintype "input"))
      (node (ref "J1") (pin "37") (pinfunction "37_37") (pintype "passive"))
    )
    (net (code "18") (name "/LA2_1") (class "Default")
      (node (ref "C11") (pin "2") (pinfunction "2_2") (pintype "passive"))
      (node (ref "IC1") (pin "G4") (pinfunction "MODDEF2/MDIO_G4") (pintype "bidirectional"))
      (node (ref "J1") (pin "35") (pinfunction "35_35") (pintype "passive"))
      (node (ref "R21") (pin "1") (pinfunction "1_1") (pintype "passive"))
    )
    (net (code "19") (name "/LA2_2") (class "Default")
      (node (ref "IC1") (pin "B1") (pinfunction "TXD1_B1") (pintype "input"))
      (node (ref "J1") (pin "33") (pinfunction "33_33") (pintype "passive"))
    )
    (net (code "20") (name "/LA2_3") (class "Default")
      (node (ref "C12") (pin "2") (pinfunction "2_2") (pintype "passive"))
      (node (ref "IC1") (pin "H3") (pinfunction "MODDEF1/MDC_H3") (pintype "input"))
      (node (ref "J1") (pin "31") (pinfunction "31_31") (pintype "passive"))
    )
    (net (code "21") (name "/LA2_4") (class "Default")
      (node (ref "IC1") (pin "C2") (pinfunction "TXD2_C2") (pintype "input"))
      (node (ref "J1") (pin "29") (pinfunction "29_29") (pintype "passive"))
    )
    (net (code "22") (name "/LA2_5") (class "Default")
      (node (ref "IC1") (pin "H4") (pinfunction "~{MDINT}_H4") (pintype "output"))
      (node (ref "J1") (pin "27") (pinfunction "27_27") (pintype "passive"))
      (node (ref "R52") (pin "1") (pinfunction "1_1") (pintype "passive"))
    )
    (net (code "23") (name "/LA2_6") (class "Default")
      (node (ref "IC1") (pin "C1") (pinfunction "TXD3_C1") (pintype "input"))
      (node (ref "J1") (pin "25") (pinfunction "25_25") (pintype "passive"))
    )
    (net (code "24") (name "/LA2_8") (class "Default")
      (node (ref "IC1") (pin "D2") (pinfunction "TXD4_D2") (pintype "input"))
      (node (ref "J1") (pin "21") (pinfunction "21_21") (pintype "passive"))
    )
    (net (code "25") (name "/LA2_10") (class "Default")
      (node (ref "IC1") (pin "D1") (pinfunction "TXD5_D1") (pintype "input"))
      (node (ref "J1") (pin "17") (pinfunction "17_17") (pintype "passive"))
    )
    (net (code "26") (name "/LA2_12") (class "Default")
      (node (ref "IC1") (pin "E2") (pinfunction "TXD6_E2") (pintype "input"))
      (node (ref "J1") (pin "13") (pinfunction "13_13") (pintype "passive"))
    )
    (net (code "27") (name "/LA2_13") (class "Default")
      (node (ref "IC1") (pin "A1") (pinfunction "TXEN_A1") (pintype "input"))
      (node (ref "J1") (pin "11") (pinfunction "11_11") (pintype "passive"))
    )
    (net (code "28") (name "/LA2_15") (class "Default")
      (node (ref "IC1") (pin "B3") (pinfunction "TXER_B3") (pintype "input"))
      (node (ref "J1") (pin "7") (pinfunction "7_7") (pintype "passive"))
    )
    (net (code "29") (name "/LA3_0") (class "Default")
      (node (ref "J2") (pin "37") (pinfunction "37_37") (pintype "passive"))
      (node (ref "R13") (pin "1") (pinfunction "1_1") (pintype "passive"))
    )
    (net (code "30") (name "/LA3_1") (class "Default")
      (node (ref "J2") (pin "35") (pinfunction "35_35") (pintype "passive"))
      (node (ref "R18") (pin "1") (pinfunction "1_1") (pintype "passive"))
    )
    (net (code "31") (name "/LA3_2") (class "Default")
      (node (ref "J2") (pin "33") (pinfunction "33_33") (pintype "passive"))
      (node (ref "R12") (pin "1") (pinfunction "1_1") (pintype "passive"))
    )
    (net (code "32") (name "/LA3_3") (class "Default")
      (node (ref "J2") (pin "31") (pinfunction "31_31") (pintype "passive"))
      (node (ref "R15") (pin "1") (pinfunction "1_1") (pintype "passive"))
    )
    (net (code "33") (name "/LA3_4") (class "Default")
      (node (ref "J2") (pin "29") (pinfunction "29_29") (pintype "passive"))
      (node (ref "R11") (pin "1") (pinfunction "1_1") (pintype "passive"))
    )
    (net (code "34") (name "/LA3_5") (class "Default")
      (node (ref "J2") (pin "27") (pinfunction "27_27") (pintype "passive"))
      (node (ref "R14") (pin "1") (pinfunction "1_1") (pintype "passive"))
    )
    (net (code "35") (name "/LA3_6") (class "Default")
      (node (ref "J2") (pin "25") (pinfunction "25_25") (pintype "passive"))
      (node (ref "R10") (pin "1") (pinfunction "1_1") (pintype "passive"))
    )
    (net (code "36") (name "/LA3_7") (class "Default")
      (node (ref "C10") (pin "2") (pinfunction "2_2") (pintype "passive"))
      (node (ref "IC1") (pin "G5") (pinfunction "TXDIS/~{SRESET}_G5") (pintype "input"))
      (node (ref "J2") (pin "23") (pinfunction "23_23") (pintype "passive"))
    )
    (net (code "37") (name "/LA3_8") (class "Default")
      (node (ref "J2") (pin "21") (pinfunction "21_21") (pintype "passive"))
      (node (ref "R6") (pin "1") (pinfunction "1_1") (pintype "passive"))
    )
    (net (code "38") (name "/LA3_9") (class "Default")
      (node (ref "J2") (pin "19") (pinfunction "19_19") (pintype "passive"))
      (node (ref "R19") (pin "1") (pinfunction "1_1") (pintype "passive"))
    )
    (net (code "39") (name "/LA3_10") (class "Default")
      (node (ref "J2") (pin "17") (pinfunction "17_17") (pintype "passive"))
      (node (ref "R5") (pin "1") (pinfunction "1_1") (pintype "passive"))
    )
    (net (code "40") (name "/LA3_11") (class "Default")
      (node (ref "C9") (pin "2") (pinfunction "2_2") (pintype "passive"))
      (node (ref "IC1") (pin "A12") (pinfunction "~{RESET}_A12") (pintype "input"))
      (node (ref "J2") (pin "15") (pinfunction "15_15") (pintype "passive"))
      (node (ref "R53") (pin "2") (pinfunction "2_2") (pintype "passive"))
    )
    (net (code "41") (name "/LA3_12") (class "Default")
      (node (ref "J2") (pin "13") (pinfunction "13_13") (pintype "passive"))
      (node (ref "R4") (pin "1") (pinfunction "1_1") (pintype "passive"))
    )
    (net (code "42") (name "/LA3_13") (class "Default")
      (node (ref "J2") (pin "11") (pinfunction "11_11") (pintype "passive"))
      (node (ref "R1") (pin "1") (pinfunction "1_1") (pintype "passive"))
    )
    (net (code "43") (name "/LA3_14") (class "Default")
      (node (ref "IC1") (pin "E1") (pinfunction "TXD7_E1") (pintype "input"))
      (node (ref "J2") (pin "9") (pinfunction "9_9") (pintype "passive"))
    )
    (net (code "44") (name "/LA3_15") (class "Default")
      (node (ref "J2") (pin "7") (pinfunction "7_7") (pintype "passive"))
      (node (ref "R16") (pin "1") (pinfunction "1_1") (pintype "passive"))
    )
    (net (code "45") (name "/LACK2") (class "Default")
      (node (ref "IC1") (pin "A2") (pinfunction "GTXCLK_A2") (pintype "input"))
      (node (ref "J1") (pin "3") (pinfunction "3_3") (pintype "passive"))
    )
    (net (code "46") (name "/LACK3") (class "Default")
      (node (ref "J2") (pin "3") (pinfunction "3_3") (pintype "passive"))
      (node (ref "R17") (pin "1") (pinfunction "1_1") (pintype "passive"))
    )
    (net (code "47") (name "/LED0") (class "Default")
      (node (ref "IC1") (pin "A13") (pinfunction "LED0_A13") (pintype "bidirectional"))
      (node (ref "R22") (pin "2") (pinfunction "2_2") (pintype "passive"))
    )
    (net (code "48") (name "/LED1") (class "Default")
      (node (ref "IC1") (pin "B12") (pinfunction "LED1_B12") (pintype "bidirectional"))
      (node (ref "R23") (pin "2") (pinfunction "2_2") (pintype "passive"))
    )
    (net (code "49") (name "/LED2") (class "Default")
      (node (ref "IC1") (pin "B13") (pinfunction "LED2_B13") (pintype "bidirectional"))
      (node (ref "R24") (pin "2") (pinfunction "2_2") (pintype "passive"))
    )
    (net (code "50") (name "/LED3") (class "Default")
      (node (ref "IC1") (pin "C12") (pinfunction "LED3_C12") (pintype "bidirectional"))
      (node (ref "R25") (pin "2") (pinfunction "2_2") (pintype "passive"))
    )
    (net (code "51") (name "/LED4") (class "Default")
      (node (ref "IC1") (pin "C13") (pinfunction "LED4_C13") (pintype "bidirectional"))
      (node (ref "R26") (pin "2") (pinfunction "2_2") (pintype "passive"))
    )
    (net (code "52") (name "/LOS") (class "Default")
      (node (ref "DD1") (pin "8") (pinfunction "LOS_8") (pintype "output"))
      (node (ref "IC1") (pin "C7") (pinfunction "RXLOS/SIGDET_C7") (pintype "output"))
      (node (ref "R9") (pin "1") (pinfunction "1_1") (pintype "passive"))
    )
    (net (code "53") (name "/MDI0_N") (class "Default")
      (node (ref "IC1") (pin "J12") (pinfunction "TXVNA_J12") (pintype "bidirectional"))
      (node (ref "J3") (pin "3") (pinfunction "3_3") (pintype "bidirectional"))
    )
    (net (code "54") (name "/MDI0_P") (class "Default")
      (node (ref "IC1") (pin "J13") (pinfunction "TXVPA_J13") (pintype "bidirectional"))
      (node (ref "J3") (pin "2") (pinfunction "2_2") (pintype "bidirectional"))
    )
    (net (code "55") (name "/MDI1_N") (class "Default")
      (node (ref "IC1") (pin "H12") (pinfunction "TXVNB_H12") (pintype "bidirectional"))
      (node (ref "J3") (pin "6") (pinfunction "6_6") (pintype "bidirectional"))
    )
    (net (code "56") (name "/MDI1_P") (class "Default")
      (node (ref "IC1") (pin "H13") (pinfunction "TXVPB_H13") (pintype "bidirectional"))
      (node (ref "J3") (pin "5") (pinfunction "5_5") (pintype "bidirectional"))
    )
    (net (code "57") (name "/MDI2_N") (class "Default")
      (node (ref "IC1") (pin "G12") (pinfunction "TXVNC_G12") (pintype "bidirectional"))
      (node (ref "J3") (pin "9") (pinfunction "9_9") (pintype "bidirectional"))
    )
    (net (code "58") (name "/MDI2_P") (class "Default")
      (node (ref "IC1") (pin "G13") (pinfunction "TXVPC_G13") (pintype "bidirectional"))
      (node (ref "J3") (pin "8") (pinfunction "8_8") (pintype "bidirectional"))
    )
    (net (code "59") (name "/MDI3_N") (class "Default")
      (node (ref "IC1") (pin "F12") (pinfunction "TXVND_F12") (pintype "bidirectional"))
      (node (ref "J3") (pin "12") (pinfunction "12_12") (pintype "bidirectional"))
    )
    (net (code "60") (name "/MDI3_P") (class "Default")
      (node (ref "IC1") (pin "F13") (pinfunction "TXVPD_F13") (pintype "bidirectional"))
      (node (ref "J3") (pin "11") (pinfunction "11_11") (pintype "bidirectional"))
    )
    (net (code "61") (name "/SCL") (class "Default")
      (node (ref "IC1") (pin "J5") (pinfunction "EECLK/PLLMODE_J5") (pintype "output"))
      (node (ref "IC2") (pin "6") (pinfunction "SCL_6") (pintype "input"))
      (node (ref "R29") (pin "1") (pinfunction "1_1") (pintype "passive"))
      (node (ref "R30") (pin "1") (pinfunction "1_1") (pintype "passive"))
      (node (ref "R32") (pin "2") (pinfunction "2_2") (pintype "passive"))
      (node (ref "W1") (pin "3") (pinfunction "3_3") (pintype "bidirectional"))
    )
    (net (code "62") (name "/SDA") (class "Default")
      (node (ref "IC1") (pin "H5") (pinfunction "EEDAT_H5") (pintype "bidirectional"))
      (node (ref "IC2") (pin "5") (pinfunction "SDA_5") (pintype "bidirectional"))
      (node (ref "R28") (pin "1") (pinfunction "1_1") (pintype "passive"))
      (node (ref "R31") (pin "1") (pinfunction "1_1") (pintype "passive"))
      (node (ref "R55") (pin "1") (pinfunction "1_1") (pintype "passive"))
      (node (ref "W1") (pin "2") (pinfunction "2_2") (pintype "bidirectional"))
    )
    (net (code "63") (name "/SFP_SCL") (class "Default")
      (node (ref "DD1") (pin "5") (pinfunction "SCL_5") (pintype "input"))
      (node (ref "R29") (pin "2") (pinfunction "2_2") (pintype "passive"))
      (node (ref "R3") (pin "1") (pinfunction "1_1") (pintype "passive"))
    )
    (net (code "64") (name "/SFP_SDA") (class "Default")
      (node (ref "DD1") (pin "4") (pinfunction "SDA_4") (pintype "bidirectional"))
      (node (ref "R2") (pin "1") (pinfunction "1_1") (pintype "passive"))
      (node (ref "R28") (pin "2") (pinfunction "2_2") (pintype "passive"))
    )
    (net (code "65") (name "GND") (class "Default")
      (node (ref "C10") (pin "1") (pinfunction "1_1") (pintype "passive"))
      (node (ref "C11") (pin "1") (pinfunction "1_1") (pintype "passive"))
      (node (ref "C12") (pin "1") (pinfunction "1_1") (pintype "passive"))
      (node (ref "C13") (pin "1") (pinfunction "1_1") (pintype "passive"))
      (node (ref "C14") (pin "1") (pinfunction "1_1") (pintype "passive"))
      (node (ref "C15") (pin "1") (pinfunction "1_1") (pintype "passive"))
      (node (ref "C16") (pin "1") (pinfunction "1_1") (pintype "passive"))
      (node (ref "C17") (pin "1") (pinfunction "1_1") (pintype "passive"))
      (node (ref "C18") (pin "1") (pinfunction "1_1") (pintype "passive"))
      (node (ref "C19") (pin "1") (pinfunction "1_1") (pintype "passive"))
      (node (ref "C20") (pin "1") (pinfunction "1_1") (pintype "passive"))
      (node (ref "C21") (pin "1") (pinfunction "1_1") (pintype "passive"))
      (node (ref "C22") (pin "1") (pinfunction "1_1") (pintype "passive"))
      (node (ref "C23") (pin "1") (pinfunction "1_1") (pintype "passive"))
      (node (ref "C24") (pin "1") (pinfunction "1_1") (pintype "passive"))
      (node (ref "C25") (pin "1") (pinfunction "1_1") (pintype "passive"))
      (node (ref "C26") (pin "1") (pinfunction "1_1") (pintype "passive"))
      (node (ref "C27") (pin "1") (pinfunction "1_1") (pintype "passive"))
      (node (ref "C28") (pin "1") (pinfunction "1_1") (pintype "passive"))
      (node (ref "C29") (pin "1") (pinfunction "1_1") (pintype "passive"))
      (node (ref "C3") (pin "1") (pinfunction "1_1") (pintype "passive"))
      (node (ref "C30") (pin "2") (pinfunction "2_2") (pintype "passive"))
      (node (ref "C31") (pin "2") (pinfunction "2_2") (pintype "passive"))
      (node (ref "C4") (pin "1") (pinfunction "1_1") (pintype "passive"))
      (node (ref "C7") (pin "1") (pinfunction "1_1") (pintype "passive"))
      (node (ref "C8") (pin "1") (pinfunction "1_1") (pintype "passive"))
      (node (ref "C9") (pin "1") (pinfunction "1_1") (pintype "passive"))
      (node (ref "DD1") (pin "1") (pinfunction "VEET_1") (pintype "power_in"))
      (node (ref "DD1") (pin "10") (pinfunction "VEER_10") (pintype "power_in"))
      (node (ref "DD1") (pin "11") (pinfunction "VEER_11") (pintype "power_in"))
      (node (ref "DD1") (pin "14") (pinfunction "VEER_14") (pintype "power_in"))
      (node (ref "DD1") (pin "17") (pinfunction "VEET_17") (pintype "power_in"))
      (node (ref "DD1") (pin "20") (pinfunction "VEET_20") (pintype "power_in"))
      (node (ref "DD1") (pin "3") (pinfunction "TX_DISABLE_3") (pintype "input"))
      (node (ref "DD2") (pin "1") (pinfunction "CAGE_1") (pintype "power_in"))
      (node (ref "DD2") (pin "10") (pinfunction "CAGE_10") (pintype "power_in"))
      (node (ref "DD2") (pin "11") (pinfunction "CAGE_11") (pintype "power_in"))
      (node (ref "DD2") (pin "12") (pinfunction "CAGE_12") (pintype "power_in"))
      (node (ref "DD2") (pin "13") (pinfunction "CAGE_13") (pintype "power_in"))
      (node (ref "DD2") (pin "14") (pinfunction "CAGE_14") (pintype "power_in"))
      (node (ref "DD2") (pin "15") (pinfunction "CAGE_15") (pintype "power_in"))
      (node (ref "DD2") (pin "16") (pinfunction "CAGE_16") (pintype "power_in"))
      (node (ref "DD2") (pin "17") (pinfunction "CAGE_17") (pintype "power_in"))
      (node (ref "DD2") (pin "18") (pinfunction "CAGE_18") (pintype "power_in"))
      (node (ref "DD2") (pin "19") (pinfunction "CAGE_19") (pintype "power_in"))
      (node (ref "DD2") (pin "2") (pinfunction "CAGE_2") (pintype "power_in"))
      (node (ref "DD2") (pin "20") (pinfunction "CAGE_20") (pintype "power_in"))
      (node (ref "DD2") (pin "3") (pinfunction "CAGE_3") (pintype "power_in"))
      (node (ref "DD2") (pin "4") (pinfunction "CAGE_4") (pintype "power_in"))
      (node (ref "DD2") (pin "5") (pinfunction "CAGE_5") (pintype "power_in"))
      (node (ref "DD2") (pin "6") (pinfunction "CAGE_6") (pintype "power_in"))
      (node (ref "DD2") (pin "7") (pinfunction "CAGE_7") (pintype "power_in"))
      (node (ref "DD2") (pin "8") (pinfunction "CAGE_8") (pintype "power_in"))
      (node (ref "DD2") (pin "9") (pinfunction "CAGE_9") (pintype "power_in"))
      (node (ref "IC1") (pin "C5") (pinfunction "VSS_C5") (pintype "passive"))
      (node (ref "IC1") (pin "D4") (pinfunction "VSS_D4") (pintype "passive"))
      (node (ref "IC1") (pin "D5") (pinfunction "VSS_D5") (pintype "passive"))
      (node (ref "IC1") (pin "D6") (pinfunction "VSS_D6") (pintype "passive"))
      (node (ref "IC1") (pin "D7") (pinfunction "VSS_D7") (pintype "passive"))
      (node (ref "IC1") (pin "D8") (pinfunction "VSS_D8") (pintype "passive"))
      (node (ref "IC1") (pin "D9") (pinfunction "VSS_D9") (pintype "passive"))
      (node (ref "IC1") (pin "E10") (pinfunction "VSS_E10") (pintype "passive"))
      (node (ref "IC1") (pin "E4") (pinfunction "VSS_E4") (pintype "passive"))
      (node (ref "IC1") (pin "E5") (pinfunction "VSS_E5") (pintype "passive"))
      (node (ref "IC1") (pin "E6") (pinfunction "VSS_E6") (pintype "passive"))
      (node (ref "IC1") (pin "E7") (pinfunction "VSS_E7") (pintype "passive"))
      (node (ref "IC1") (pin "E8") (pinfunction "VSS_E8") (pintype "passive"))
      (node (ref "IC1") (pin "E9") (pinfunction "VSS_E9") (pintype "passive"))
      (node (ref "IC1") (pin "F5") (pinfunction "VSS_F5") (pintype "passive"))
      (node (ref "IC1") (pin "F6") (pinfunction "VSS_F6") (pintype "passive"))
      (node (ref "IC1") (pin "F7") (pinfunction "VSS_F7") (pintype "passive"))
      (node (ref "IC1") (pin "F8") (pinfunction "VSS_F8") (pintype "passive"))
      (node (ref "IC1") (pin "F9") (pinfunction "VSS_F9") (pintype "passive"))
      (node (ref "IC1") (pin "H11") (pinfunction "VSS_H11") (pintype "passive"))
      (node (ref "IC1") (pin "H9") (pinfunction "VSS_H9") (pintype "passive"))
      (node (ref "IC1") (pin "J11") (pinfunction "VSS_J11") (pintype "passive"))
      (node (ref "IC1") (pin "J7") (pinfunction "VSS_J7") (pintype "passive"))
      (node (ref "IC1") (pin "J9") (pinfunction "VSS_J9") (pintype "passive"))
      (node (ref "IC2") (pin "4") (pinfunction "VSS_4") (pintype "power_in"))
      (node (ref "IC2") (pin "7") (pinfunction "WP_7") (pintype "input"))
      (node (ref "IC4") (pin "1") (pinfunction "GND_1") (pintype "power_in"))
      (node (ref "J1") (pin "10") (pinfunction "10_10") (pintype "passive"))
      (node (ref "J1") (pin "12") (pinfunction "12_12") (pintype "passive"))
      (node (ref "J1") (pin "14") (pinfunction "14_14") (pintype "passive"))
      (node (ref "J1") (pin "16") (pinfunction "16_16") (pintype "passive"))
      (node (ref "J1") (pin "18") (pinfunction "18_18") (pintype "passive"))
      (node (ref "J1") (pin "2") (pinfunction "2_2") (pintype "passive"))
      (node (ref "J1") (pin "20") (pinfunction "20_20") (pintype "passive"))
      (node (ref "J1") (pin "22") (pinfunction "22_22") (pintype "passive"))
      (node (ref "J1") (pin "24") (pinfunction "24_24") (pintype "passive"))
      (node (ref "J1") (pin "26") (pinfunction "26_26") (pintype "passive"))
      (node (ref "J1") (pin "28") (pinfunction "28_28") (pintype "passive"))
      (node (ref "J1") (pin "30") (pinfunction "30_30") (pintype "passive"))
      (node (ref "J1") (pin "32") (pinfunction "32_32") (pintype "passive"))
      (node (ref "J1") (pin "34") (pinfunction "34_34") (pintype "passive"))
      (node (ref "J1") (pin "36") (pinfunction "36_36") (pintype "passive"))
      (node (ref "J1") (pin "38") (pinfunction "38_38") (pintype "passive"))
      (node (ref "J1") (pin "4") (pinfunction "4_4") (pintype "passive"))
      (node (ref "J1") (pin "40") (pinfunction "40_40") (pintype "passive"))
      (node (ref "J1") (pin "6") (pinfunction "6_6") (pintype "passive"))
      (node (ref "J1") (pin "8") (pinfunction "8_8") (pintype "passive"))
      (node (ref "J2") (pin "10") (pinfunction "10_10") (pintype "passive"))
      (node (ref "J2") (pin "12") (pinfunction "12_12") (pintype "passive"))
      (node (ref "J2") (pin "14") (pinfunction "14_14") (pintype "passive"))
      (node (ref "J2") (pin "16") (pinfunction "16_16") (pintype "passive"))
      (node (ref "J2") (pin "18") (pinfunction "18_18") (pintype "passive"))
      (node (ref "J2") (pin "2") (pinfunction "2_2") (pintype "passive"))
      (node (ref "J2") (pin "20") (pinfunction "20_20") (pintype "passive"))
      (node (ref "J2") (pin "22") (pinfunction "22_22") (pintype "passive"))
      (node (ref "J2") (pin "24") (pinfunction "24_24") (pintype "passive"))
      (node (ref "J2") (pin "26") (pinfunction "26_26") (pintype "passive"))
      (node (ref "J2") (pin "28") (pinfunction "28_28") (pintype "passive"))
      (node (ref "J2") (pin "30") (pinfunction "30_30") (pintype "passive"))
      (node (ref "J2") (pin "32") (pinfunction "32_32") (pintype "passive"))
      (node (ref "J2") (pin "34") (pinfunction "34_34") (pintype "passive"))
      (node (ref "J2") (pin "36") (pinfunction "36_36") (pintype "passive"))
      (node (ref "J2") (pin "38") (pinfunction "38_38") (pintype "passive"))
      (node (ref "J2") (pin "4") (pinfunction "4_4") (pintype "passive"))
      (node (ref "J2") (pin "40") (pinfunction "40_40") (pintype "passive"))
      (node (ref "J2") (pin "6") (pinfunction "6_6") (pintype "passive"))
      (node (ref "J2") (pin "8") (pinfunction "8_8") (pintype "passive"))
      (node (ref "J3") (pin "1") (pinfunction "1_1") (pintype "bidirectional"))
      (node (ref "J3") (pin "10") (pinfunction "10_10") (pintype "bidirectional"))
      (node (ref "J3") (pin "13") (pinfunction "13_13") (pintype "bidirectional"))
      (node (ref "J3") (pin "4") (pinfunction "4_4") (pintype "bidirectional"))
      (node (ref "J4") (pin "2") (pinfunction "2_2") (pintype "bidirectional"))
      (node (ref "Q1") (pin "2") (pinfunction "GND_2") (pintype "power_in"))
      (node (ref "Q1") (pin "4") (pinfunction "GND_4") (pintype "power_in"))
      (node (ref "R20") (pin "1") (pinfunction "1_1") (pintype "passive"))
      (node (ref "R27") (pin "1") (pinfunction "1_1") (pintype "passive"))
      (node (ref "R32") (pin "1") (pinfunction "1_1") (pintype "passive"))
      (node (ref "R33") (pin "1") (pinfunction "1_1") (pintype "passive"))
      (node (ref "R34") (pin "1") (pinfunction "1_1") (pintype "passive"))
      (node (ref "R35") (pin "1") (pinfunction "1_1") (pintype "passive"))
      (node (ref "R36") (pin "1") (pinfunction "1_1") (pintype "passive"))
      (node (ref "R45") (pin "1") (pinfunction "1_1") (pintype "passive"))
      (node (ref "R46") (pin "1") (pinfunction "1_1") (pintype "passive"))
      (node (ref "R47") (pin "1") (pinfunction "1_1") (pintype "passive"))
      (node (ref "R48") (pin "1") (pinfunction "1_1") (pintype "passive"))
      (node (ref "R49") (pin "1") (pinfunction "1_1") (pintype "passive"))
      (node (ref "R50") (pin "1") (pinfunction "1_1") (pintype "passive"))
      (node (ref "R51") (pin "1") (pinfunction "1_1") (pintype "passive"))
      (node (ref "R53") (pin "1") (pinfunction "1_1") (pintype "passive"))
      (node (ref "R55") (pin "2") (pinfunction "2_2") (pintype "passive"))
      (node (ref "W1") (pin "1") (pinfunction "1_1") (pintype "bidirectional"))
    )
    (net (code "66") (name "Net-(C20-Pad2)") (class "Default")
      (node (ref "C20") (pin "2") (pinfunction "2_2") (pintype "passive"))
      (node (ref "C21") (pin "2") (pinfunction "2_2") (pintype "passive"))
      (node (ref "C22") (pin "2") (pinfunction "2_2") (pintype "passive"))
      (node (ref "C23") (pin "2") (pinfunction "2_2") (pintype "passive"))
      (node (ref "IC1") (pin "F10") (pinfunction "VDD33A_F10") (pintype "passive"))
      (node (ref "IC1") (pin "G10") (pinfunction "VDD33A_G10") (pintype "passive"))
      (node (ref "IC1") (pin "G8") (pinfunction "VDD33A_G8") (pintype "passive"))
      (node (ref "IC1") (pin "G9") (pinfunction "VDD33A_G9") (pintype "passive"))
      (node (ref "L3") (pin "2") (pinfunction "2_2") (pintype "passive"))
    )
    (net (code "67") (name "Net-(C24-Pad2)") (class "Default")
      (node (ref "C24") (pin "2") (pinfunction "2_2") (pintype "passive"))
      (node (ref "C25") (pin "2") (pinfunction "2_2") (pintype "passive"))
      (node (ref "C26") (pin "2") (pinfunction "2_2") (pintype "passive"))
      (node (ref "C27") (pin "2") (pinfunction "2_2") (pintype "passive"))
      (node (ref "IC1") (pin "C10") (pinfunction "VDD12_C10") (pintype "passive"))
      (node (ref "IC1") (pin "C11") (pinfunction "VDD12_C11") (pintype "passive"))
      (node (ref "IC1") (pin "F3") (pinfunction "VDD12_F3") (pintype "passive"))
      (node (ref "IC1") (pin "F4") (pinfunction "VDD12_F4") (pintype "passive"))
      (node (ref "IC1") (pin "G3") (pinfunction "VDD12_G3") (pintype "passive"))
      (node (ref "L5") (pin "2") (pinfunction "2_2") (pintype "passive"))
    )
    (net (code "68") (name "Net-(DD1-RS0)") (class "Default")
      (node (ref "DD1") (pin "7") (pinfunction "RS0_7") (pintype "input"))
      (node (ref "R7") (pin "1") (pinfunction "1_1") (pintype "passive"))
    )
    (net (code "69") (name "Net-(DD1-RS1)") (class "Default")
      (node (ref "DD1") (pin "9") (pinfunction "RS1_9") (pintype "input"))
      (node (ref "R8") (pin "1") (pinfunction "1_1") (pintype "passive"))
    )
    (net (code "70") (name "Net-(DD1-VCCR)") (class "Default")
      (node (ref "C3") (pin "2") (pinfunction "2_2") (pintype "passive"))
      (node (ref "C4") (pin "2") (pinfunction "2_2") (pintype "passive"))
      (node (ref "DD1") (pin "15") (pinfunction "VCCR_15") (pintype "power_in"))
      (node (ref "L1") (pin "2") (pinfunction "2_2") (pintype "passive"))
    )
    (net (code "71") (name "Net-(DD1-VCCT)") (class "Default")
      (node (ref "C7") (pin "2") (pinfunction "2_2") (pintype "passive"))
      (node (ref "C8") (pin "2") (pinfunction "2_2") (pintype "passive"))
      (node (ref "DD1") (pin "16") (pinfunction "VCCT_16") (pintype "power_in"))
      (node (ref "L2") (pin "2") (pinfunction "2_2") (pintype "passive"))
    )
    (net (code "72") (name "Net-(IC1A-COL)") (class "Default")
      (node (ref "IC1") (pin "B4") (pinfunction "COL_B4") (pintype "output"))
      (node (ref "R18") (pin "2") (pinfunction "2_2") (pintype "passive"))
    )
    (net (code "73") (name "Net-(IC1A-CRS)") (class "Default")
      (node (ref "IC1") (pin "C4") (pinfunction "CRS_C4") (pintype "output"))
      (node (ref "R19") (pin "2") (pinfunction "2_2") (pintype "passive"))
    )
    (net (code "74") (name "Net-(IC1A-RXCLK)") (class "Default")
      (node (ref "IC1") (pin "B5") (pinfunction "RXCLK_B5") (pintype "output"))
      (node (ref "R16") (pin "2") (pinfunction "2_2") (pintype "passive"))
    )
    (net (code "75") (name "Net-(IC1A-RXD0)") (class "Default")
      (node (ref "IC1") (pin "B6") (pinfunction "RXD0_B6") (pintype "output"))
      (node (ref "R13") (pin "2") (pinfunction "2_2") (pintype "passive"))
    )
    (net (code "76") (name "Net-(IC1A-RXD1)") (class "Default")
      (node (ref "IC1") (pin "A6") (pinfunction "RXD1_A6") (pintype "output"))
      (node (ref "R12") (pin "2") (pinfunction "2_2") (pintype "passive"))
    )
    (net (code "77") (name "Net-(IC1A-RXD2)") (class "Default")
      (node (ref "IC1") (pin "B7") (pinfunction "RXD2_B7") (pintype "output"))
      (node (ref "R11") (pin "2") (pinfunction "2_2") (pintype "passive"))
    )
    (net (code "78") (name "Net-(IC1A-RXD3)") (class "Default")
      (node (ref "IC1") (pin "A7") (pinfunction "RXD3_A7") (pintype "output"))
      (node (ref "R10") (pin "2") (pinfunction "2_2") (pintype "passive"))
    )
    (net (code "79") (name "Net-(IC1A-RXD4)") (class "Default")
      (node (ref "IC1") (pin "B8") (pinfunction "RXD4_B8") (pintype "output"))
      (node (ref "R6") (pin "2") (pinfunction "2_2") (pintype "passive"))
    )
    (net (code "80") (name "Net-(IC1A-RXD5)") (class "Default")
      (node (ref "IC1") (pin "A8") (pinfunction "RXD5_A8") (pintype "output"))
      (node (ref "R5") (pin "2") (pinfunction "2_2") (pintype "passive"))
    )
    (net (code "81") (name "Net-(IC1A-RXD6)") (class "Default")
      (node (ref "IC1") (pin "B9") (pinfunction "RXD6_B9") (pintype "output"))
      (node (ref "R4") (pin "2") (pinfunction "2_2") (pintype "passive"))
    )
    (net (code "82") (name "Net-(IC1A-RXD7)") (class "Default")
      (node (ref "IC1") (pin "A9") (pinfunction "RXD7_A9") (pintype "output"))
      (node (ref "R1") (pin "2") (pinfunction "2_2") (pintype "passive"))
    )
    (net (code "83") (name "Net-(IC1A-RXDV)") (class "Default")
      (node (ref "IC1") (pin "A5") (pinfunction "RXDV_A5") (pintype "output"))
      (node (ref "R14") (pin "2") (pinfunction "2_2") (pintype "passive"))
    )
    (net (code "84") (name "Net-(IC1A-RXER)") (class "Default")
      (node (ref "IC1") (pin "A4") (pinfunction "RXER_A4") (pintype "output"))
      (node (ref "R15") (pin "2") (pinfunction "2_2") (pintype "passive"))
    )
    (net (code "85") (name "Net-(IC1A-TXCLK)") (class "Default")
      (node (ref "IC1") (pin "A3") (pinfunction "TXCLK_A3") (pintype "output"))
      (node (ref "R17") (pin "2") (pinfunction "2_2") (pintype "passive"))
    )
    (net (code "86") (name "Net-(IC1B-SCLKN)") (class "Default")
      (node (ref "IC1") (pin "J2") (pinfunction "SCLKN_J2") (pintype "input"))
      (node (ref "TP6") (pin "1") (pinfunction "1_1") (pintype "bidirectional"))
    )
    (net (code "87") (name "Net-(IC1B-SCLKP)") (class "Default")
      (node (ref "IC1") (pin "J1") (pinfunction "SCLKP_J1") (pintype "input"))
      (node (ref "TP5") (pin "1") (pinfunction "1_1") (pintype "bidirectional"))
    )
    (net (code "88") (name "Net-(IC1B-SDIN)") (class "Default")
      (node (ref "IC1") (pin "G1") (pinfunction "SDIN_G1") (pintype "input"))
      (node (ref "TP4") (pin "1") (pinfunction "1_1") (pintype "bidirectional"))
    )
    (net (code "89") (name "Net-(IC1B-SDIP)") (class "Default")
      (node (ref "IC1") (pin "G2") (pinfunction "SDIP_G2") (pintype "input"))
      (node (ref "TP3") (pin "1") (pinfunction "1_1") (pintype "bidirectional"))
    )
    (net (code "90") (name "Net-(IC1B-SDON)") (class "Default")
      (node (ref "IC1") (pin "F1") (pinfunction "SDON_F1") (pintype "output"))
      (node (ref "TP2") (pin "1") (pinfunction "1_1") (pintype "bidirectional"))
    )
    (net (code "91") (name "Net-(IC1B-SDOP)") (class "Default")
      (node (ref "IC1") (pin "F2") (pinfunction "SDOP_F2") (pintype "output"))
      (node (ref "TP1") (pin "1") (pinfunction "1_1") (pintype "bidirectional"))
    )
    (net (code "92") (name "Net-(IC1D-CLKOUTMICRO{slash}~{OSCDIS})") (class "Default")
      (node (ref "IC1") (pin "G6") (pinfunction "CLKOUTMICRO/~{OSCDIS}_G6") (pintype "output"))
      (node (ref "R54") (pin "2") (pinfunction "2_2") (pintype "passive"))
    )
    (net (code "93") (name "Net-(IC1D-MODDEF0{slash}CLKOUTMAC)") (class "Default")
      (node (ref "IC1") (pin "A10") (pinfunction "MODDEF0/CLKOUTMAC_A10") (pintype "output"))
      (node (ref "TP7") (pin "1") (pinfunction "1_1") (pintype "bidirectional"))
    )
    (net (code "94") (name "Net-(IC1D-REFFILT)") (class "Default")
      (node (ref "C13") (pin "2") (pinfunction "2_2") (pintype "passive"))
      (node (ref "IC1") (pin "H6") (pinfunction "REFFILT_H6") (pintype "input"))
    )
    (net (code "95") (name "Net-(IC1D-REFREXT)") (class "Default")
      (node (ref "IC1") (pin "J6") (pinfunction "REFREXT_J6") (pintype "input"))
      (node (ref "R27") (pin "2") (pinfunction "2_2") (pintype "passive"))
    )
    (net (code "96") (name "Net-(IC1D-XTAL1{slash}REFCLK)") (class "Default")
      (node (ref "C15") (pin "2") (pinfunction "2_2") (pintype "passive"))
      (node (ref "IC1") (pin "J10") (pinfunction "XTAL1/REFCLK_J10") (pintype "input"))
      (node (ref "Q1") (pin "1") (pinfunction "X_1") (pintype "passive"))
    )
    (net (code "97") (name "Net-(IC1D-XTAL2)") (class "Default")
      (node (ref "C14") (pin "2") (pinfunction "2_2") (pintype "passive"))
      (node (ref "IC1") (pin "H10") (pinfunction "XTAL2_H10") (pintype "output"))
      (node (ref "Q1") (pin "3") (pinfunction "X_3") (pintype "passive"))
    )
    (net (code "98") (name "Net-(IC1E-TCK)") (class "Default")
      (node (ref "IC1") (pin "C9") (pinfunction "TCK_C9") (pintype "input"))
      (node (ref "TP11") (pin "1") (pinfunction "1_1") (pintype "bidirectional"))
    )
    (net (code "99") (name "Net-(IC1E-TDI)") (class "Default")
      (node (ref "IC1") (pin "A11") (pinfunction "TDI_A11") (pintype "input"))
      (node (ref "TP8") (pin "1") (pinfunction "1_1") (pintype "bidirectional"))
    )
    (net (code "100") (name "Net-(IC1E-TDO)") (class "Default")
      (node (ref "IC1") (pin "B11") (pinfunction "TDO_B11") (pintype "output"))
      (node (ref "TP9") (pin "1") (pinfunction "1_1") (pintype "bidirectional"))
    )
    (net (code "101") (name "Net-(IC1E-TMS)") (class "Default")
      (node (ref "IC1") (pin "B10") (pinfunction "TMS_B10") (pintype "input"))
      (node (ref "TP10") (pin "1") (pinfunction "1_1") (pintype "bidirectional"))
    )
    (net (code "102") (name "Net-(IC1E-~{TRST})") (class "Default")
      (node (ref "IC1") (pin "C8") (pinfunction "~{TRST}_C8") (pintype "input"))
      (node (ref "R36") (pin "2") (pinfunction "2_2") (pintype "passive"))
    )
    (net (code "103") (name "Net-(IC1F-VDD12A)") (class "Default")
      (node (ref "C28") (pin "2") (pinfunction "2_2") (pintype "passive"))
      (node (ref "C29") (pin "2") (pinfunction "2_2") (pintype "passive"))
      (node (ref "IC1") (pin "H7") (pinfunction "VDD12A_H7") (pintype "passive"))
      (node (ref "L4") (pin "2") (pinfunction "2_2") (pintype "passive"))
    )
    (net (code "104") (name "Net-(IC2-A0)") (class "Default")
      (node (ref "IC2") (pin "1") (pinfunction "A0_1") (pintype "input"))
      (node (ref "R35") (pin "2") (pinfunction "2_2") (pintype "passive"))
    )
    (net (code "105") (name "Net-(IC2-A1)") (class "Default")
      (node (ref "IC2") (pin "2") (pinfunction "A1_2") (pintype "input"))
      (node (ref "R34") (pin "2") (pinfunction "2_2") (pintype "passive"))
    )
    (net (code "106") (name "Net-(IC2-A2)") (class "Default")
      (node (ref "IC2") (pin "3") (pinfunction "A2_3") (pintype "input"))
      (node (ref "R33") (pin "2") (pinfunction "2_2") (pintype "passive"))
    )
    (net (code "107") (name "Net-(LD1-C)") (class "Default")
      (node (ref "LD1") (pin "1") (pinfunction "C_1") (pintype "passive"))
      (node (ref "R22") (pin "1") (pinfunction "1_1") (pintype "passive"))
    )
    (net (code "108") (name "Net-(LD2-C)") (class "Default")
      (node (ref "LD2") (pin "1") (pinfunction "C_1") (pintype "passive"))
      (node (ref "R23") (pin "1") (pinfunction "1_1") (pintype "passive"))
    )
    (net (code "109") (name "Net-(LD3-C)") (class "Default")
      (node (ref "LD3") (pin "1") (pinfunction "C_1") (pintype "passive"))
      (node (ref "R24") (pin "1") (pinfunction "1_1") (pintype "passive"))
    )
    (net (code "110") (name "Net-(LD4-C)") (class "Default")
      (node (ref "LD4") (pin "1") (pinfunction "C_1") (pintype "passive"))
      (node (ref "R25") (pin "1") (pinfunction "1_1") (pintype "passive"))
    )
    (net (code "111") (name "Net-(LD5-C)") (class "Default")
      (node (ref "LD5") (pin "1") (pinfunction "C_1") (pintype "passive"))
      (node (ref "R26") (pin "1") (pinfunction "1_1") (pintype "passive"))
    )
    (net (code "112") (name "P1V2") (class "Default")
      (node (ref "C31") (pin "1") (pinfunction "1_1") (pintype "passive"))
      (node (ref "IC4") (pin "3") (pinfunction "OUT_3") (pintype "power_in"))
      (node (ref "L4") (pin "1") (pinfunction "1_1") (pintype "passive"))
      (node (ref "L5") (pin "1") (pinfunction "1_1") (pintype "passive"))
    )
    (net (code "113") (name "P3V3") (class "Default")
      (node (ref "C16") (pin "2") (pinfunction "2_2") (pintype "passive"))
      (node (ref "C17") (pin "2") (pinfunction "2_2") (pintype "passive"))
      (node (ref "C18") (pin "2") (pinfunction "2_2") (pintype "passive"))
      (node (ref "C19") (pin "2") (pinfunction "2_2") (pintype "passive"))
      (node (ref "C30") (pin "1") (pinfunction "1_1") (pintype "passive"))
      (node (ref "IC1") (pin "C3") (pinfunction "VDDIOMAC_C3") (pintype "passive"))
      (node (ref "IC1") (pin "C6") (pinfunction "VDDIOMAC_C6") (pintype "passive"))
      (node (ref "IC1") (pin "D10") (pinfunction "VDDIOCTRL_D10") (pintype "passive"))
      (node (ref "IC1") (pin "D3") (pinfunction "VDDIOMAC_D3") (pintype "passive"))
      (node (ref "IC1") (pin "G7") (pinfunction "VDDIOMICRO_G7") (pintype "passive"))
      (node (ref "IC2") (pin "8") (pinfunction "VCC_8") (pintype "power_in"))
      (node (ref "IC4") (pin "2") (pinfunction "IN_2") (pintype "input"))
      (node (ref "J4") (pin "1") (pinfunction "1_1") (pintype "bidirectional"))
      (node (ref "L1") (pin "1") (pinfunction "1_1") (pintype "passive"))
      (node (ref "L2") (pin "1") (pinfunction "1_1") (pintype "passive"))
      (node (ref "L3") (pin "1") (pinfunction "1_1") (pintype "passive"))
      (node (ref "LD1") (pin "2") (pinfunction "A_2") (pintype "passive"))
      (node (ref "LD2") (pin "2") (pinfunction "A_2") (pintype "passive"))
      (node (ref "LD3") (pin "2") (pinfunction "A_2") (pintype "passive"))
      (node (ref "LD4") (pin "2") (pinfunction "A_2") (pintype "passive"))
      (node (ref "LD5") (pin "2") (pinfunction "A_2") (pintype "passive"))
      (node (ref "R2") (pin "2") (pinfunction "2_2") (pintype "passive"))
      (node (ref "R21") (pin "2") (pinfunction "2_2") (pintype "passive"))
      (node (ref "R3") (pin "2") (pinfunction "2_2") (pintype "passive"))
      (node (ref "R30") (pin "2") (pinfunction "2_2") (pintype "passive"))
      (node (ref "R31") (pin "2") (pinfunction "2_2") (pintype "passive"))
      (node (ref "R37") (pin "2") (pinfunction "2_2") (pintype "passive"))
      (node (ref "R38") (pin "2") (pinfunction "2_2") (pintype "passive"))
      (node (ref "R39") (pin "2") (pinfunction "2_2") (pintype "passive"))
      (node (ref "R40") (pin "2") (pinfunction "2_2") (pintype "passive"))
      (node (ref "R41") (pin "2") (pinfunction "2_2") (pintype "passive"))
      (node (ref "R42") (pin "2") (pinfunction "2_2") (pintype "passive"))
      (node (ref "R43") (pin "2") (pinfunction "2_2") (pintype "passive"))
      (node (ref "R44") (pin "2") (pinfunction "2_2") (pintype "passive"))
      (node (ref "R52") (pin "2") (pinfunction "2_2") (pintype "passive"))
      (node (ref "R54") (pin "1") (pinfunction "1_1") (pintype "passive"))
      (node (ref "R7") (pin "2") (pinfunction "2_2") (pintype "passive"))
      (node (ref "R8") (pin "2") (pinfunction "2_2") (pintype "passive"))
      (node (ref "R9") (pin "2") (pinfunction "2_2") (pintype "passive"))
      (node (ref "W1") (pin "4") (pinfunction "4_4") (pintype "bidirectional"))
    )
    (net (code "114") (name "unconnected-(DD1-MOD_ABS-Pad6)") (class "Default")
      (node (ref "DD1") (pin "6") (pinfunction "MOD_ABS_6") (pintype "output+no_connect"))
    )
    (net (code "115") (name "unconnected-(DD1-TX_FAULT-Pad2)") (class "Default")
      (node (ref "DD1") (pin "2") (pinfunction "TX_FAULT_2") (pintype "output+no_connect"))
    )
    (net (code "116") (name "unconnected-(IC1F-NC-PadE3)") (class "Default")
      (node (ref "IC1") (pin "E3") (pinfunction "NC_E3") (pintype "passive"))
    )
    (net (code "117") (name "unconnected-(IC1F-NC-PadH8)") (class "Default")
      (node (ref "IC1") (pin "H8") (pinfunction "NC_H8") (pintype "passive"))
    )
    (net (code "118") (name "unconnected-(IC1F-NC-PadJ8)") (class "Default")
      (node (ref "IC1") (pin "J8") (pinfunction "NC_J8") (pintype "passive"))
    )
    (net (code "119") (name "unconnected-(J1-Pad1)") (class "Default")
      (node (ref "J1") (pin "1") (pinfunction "1_1") (pintype "passive+no_connect"))
    )
    (net (code "120") (name "unconnected-(J1-Pad5)") (class "Default")
      (node (ref "J1") (pin "5") (pinfunction "5_5") (pintype "passive+no_connect"))
    )
    (net (code "121") (name "unconnected-(J1-Pad9)") (class "Default")
      (node (ref "J1") (pin "9") (pinfunction "9_9") (pintype "passive+no_connect"))
    )
    (net (code "122") (name "unconnected-(J1-Pad15)") (class "Default")
      (node (ref "J1") (pin "15") (pinfunction "15_15") (pintype "passive+no_connect"))
    )
    (net (code "123") (name "unconnected-(J1-Pad19)") (class "Default")
      (node (ref "J1") (pin "19") (pinfunction "19_19") (pintype "passive+no_connect"))
    )
    (net (code "124") (name "unconnected-(J1-Pad23)") (class "Default")
      (node (ref "J1") (pin "23") (pinfunction "23_23") (pintype "passive+no_connect"))
    )
    (net (code "125") (name "unconnected-(J1-Pad39)") (class "Default")
      (node (ref "J1") (pin "39") (pinfunction "39_39") (pintype "passive+no_connect"))
    )
    (net (code "126") (name "unconnected-(J2-Pad1)") (class "Default")
      (node (ref "J2") (pin "1") (pinfunction "1_1") (pintype "passive+no_connect"))
    )
    (net (code "127") (name "unconnected-(J2-Pad5)") (class "Default")
      (node (ref "J2") (pin "5") (pinfunction "5_5") (pintype "passive+no_connect"))
    )
    (net (code "128") (name "unconnected-(J2-Pad39)") (class "Default")
      (node (ref "J2") (pin "39") (pinfunction "39_39") (pintype "passive+no_connect"))
    )
    (net (code "129") (name "unconnected-(J3-Pad7)") (class "Default")
      (node (ref "J3") (pin "7") (pinfunction "7_7") (pintype "bidirectional+no_connect"))
    )
    (net (code "130") (name "unconnected-(J3-Pad14)") (class "Default")
      (node (ref "J3") (pin "14") (pinfunction "14_14") (pintype "bidirectional+no_connect"))
    )
  )
)
